# disciples_v1.net
KiCad netlist of a schematic drawn in EAGLE
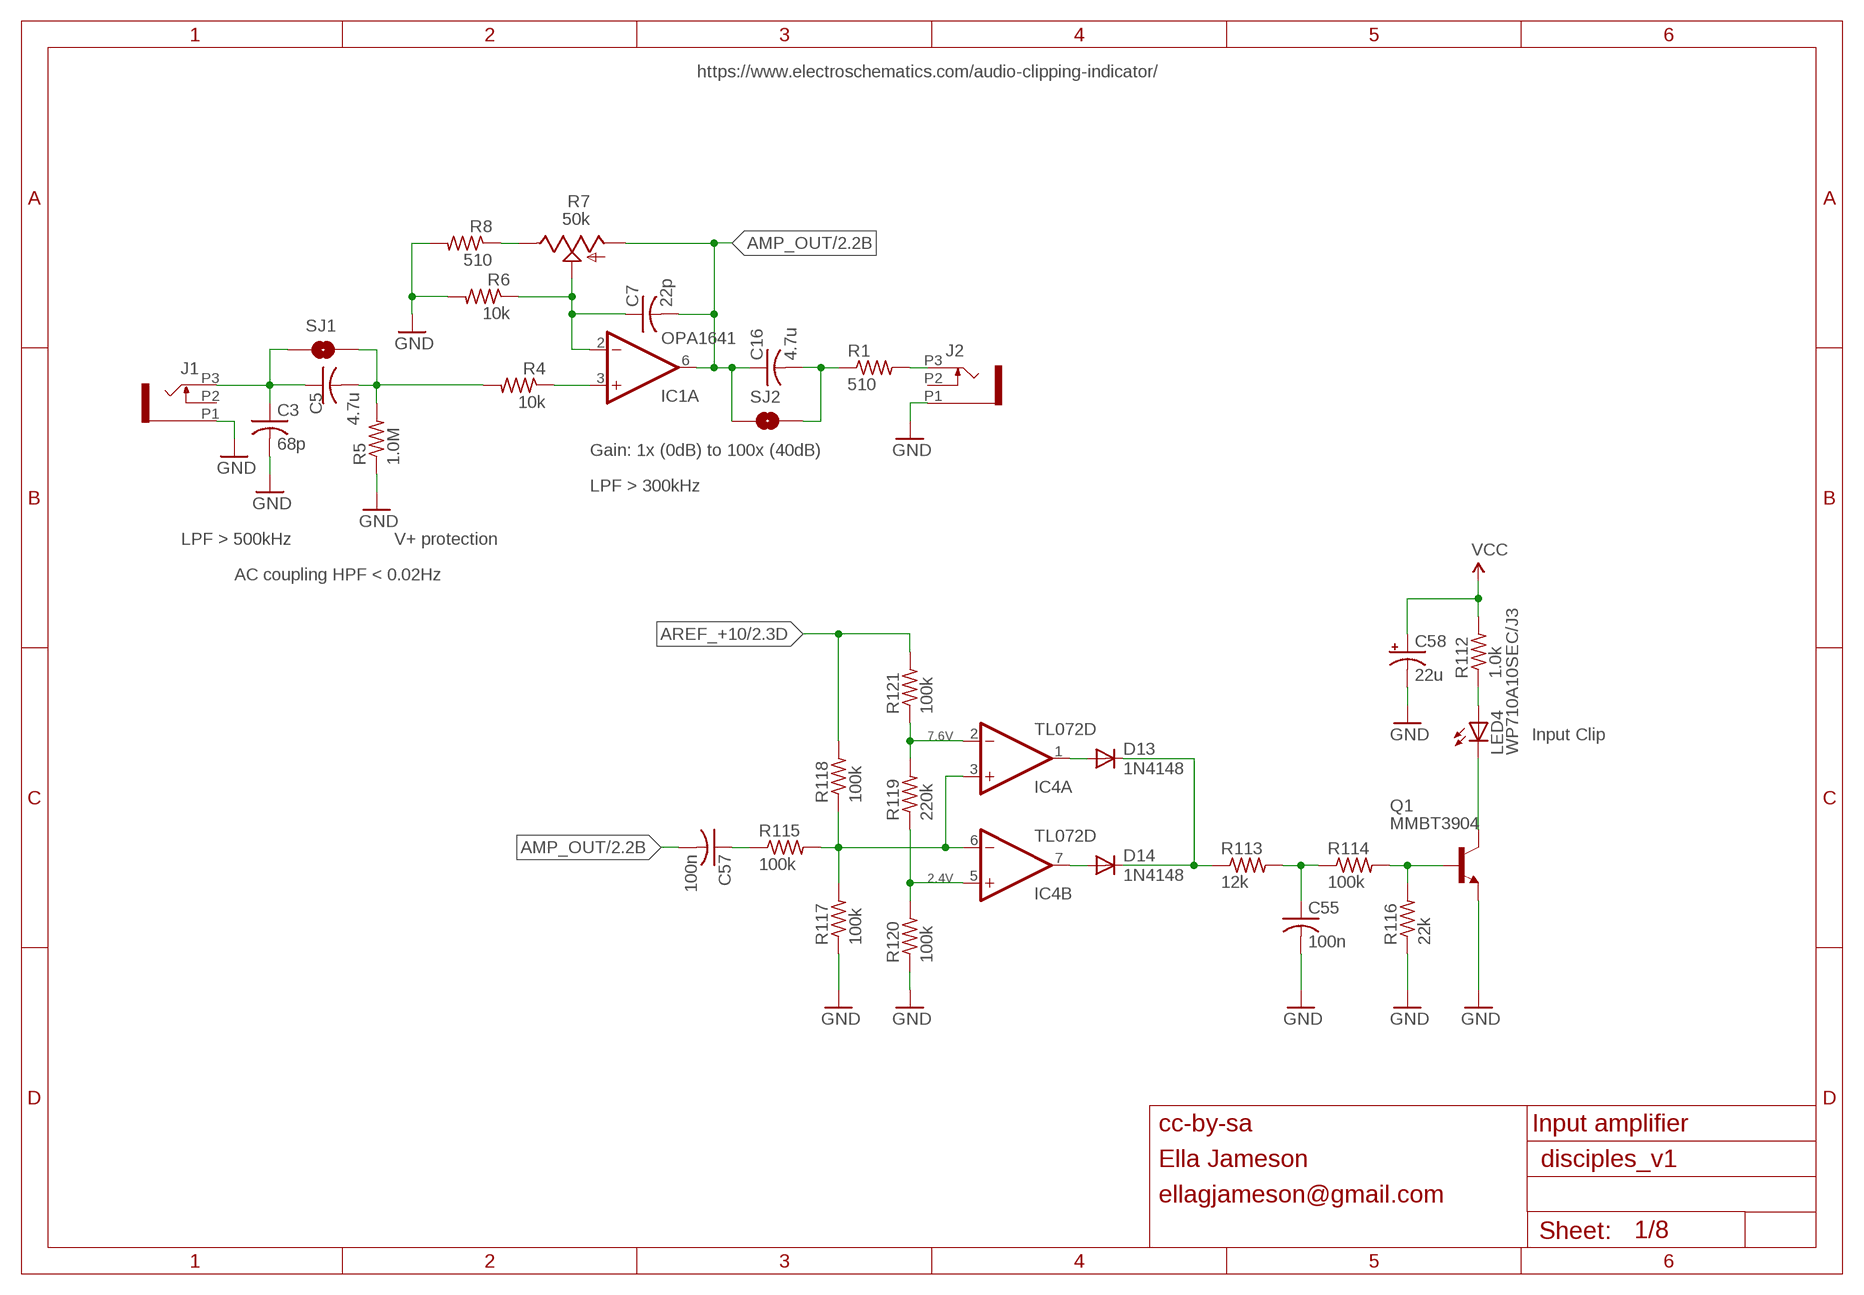
[diagram p0: schematic, sheet 1]
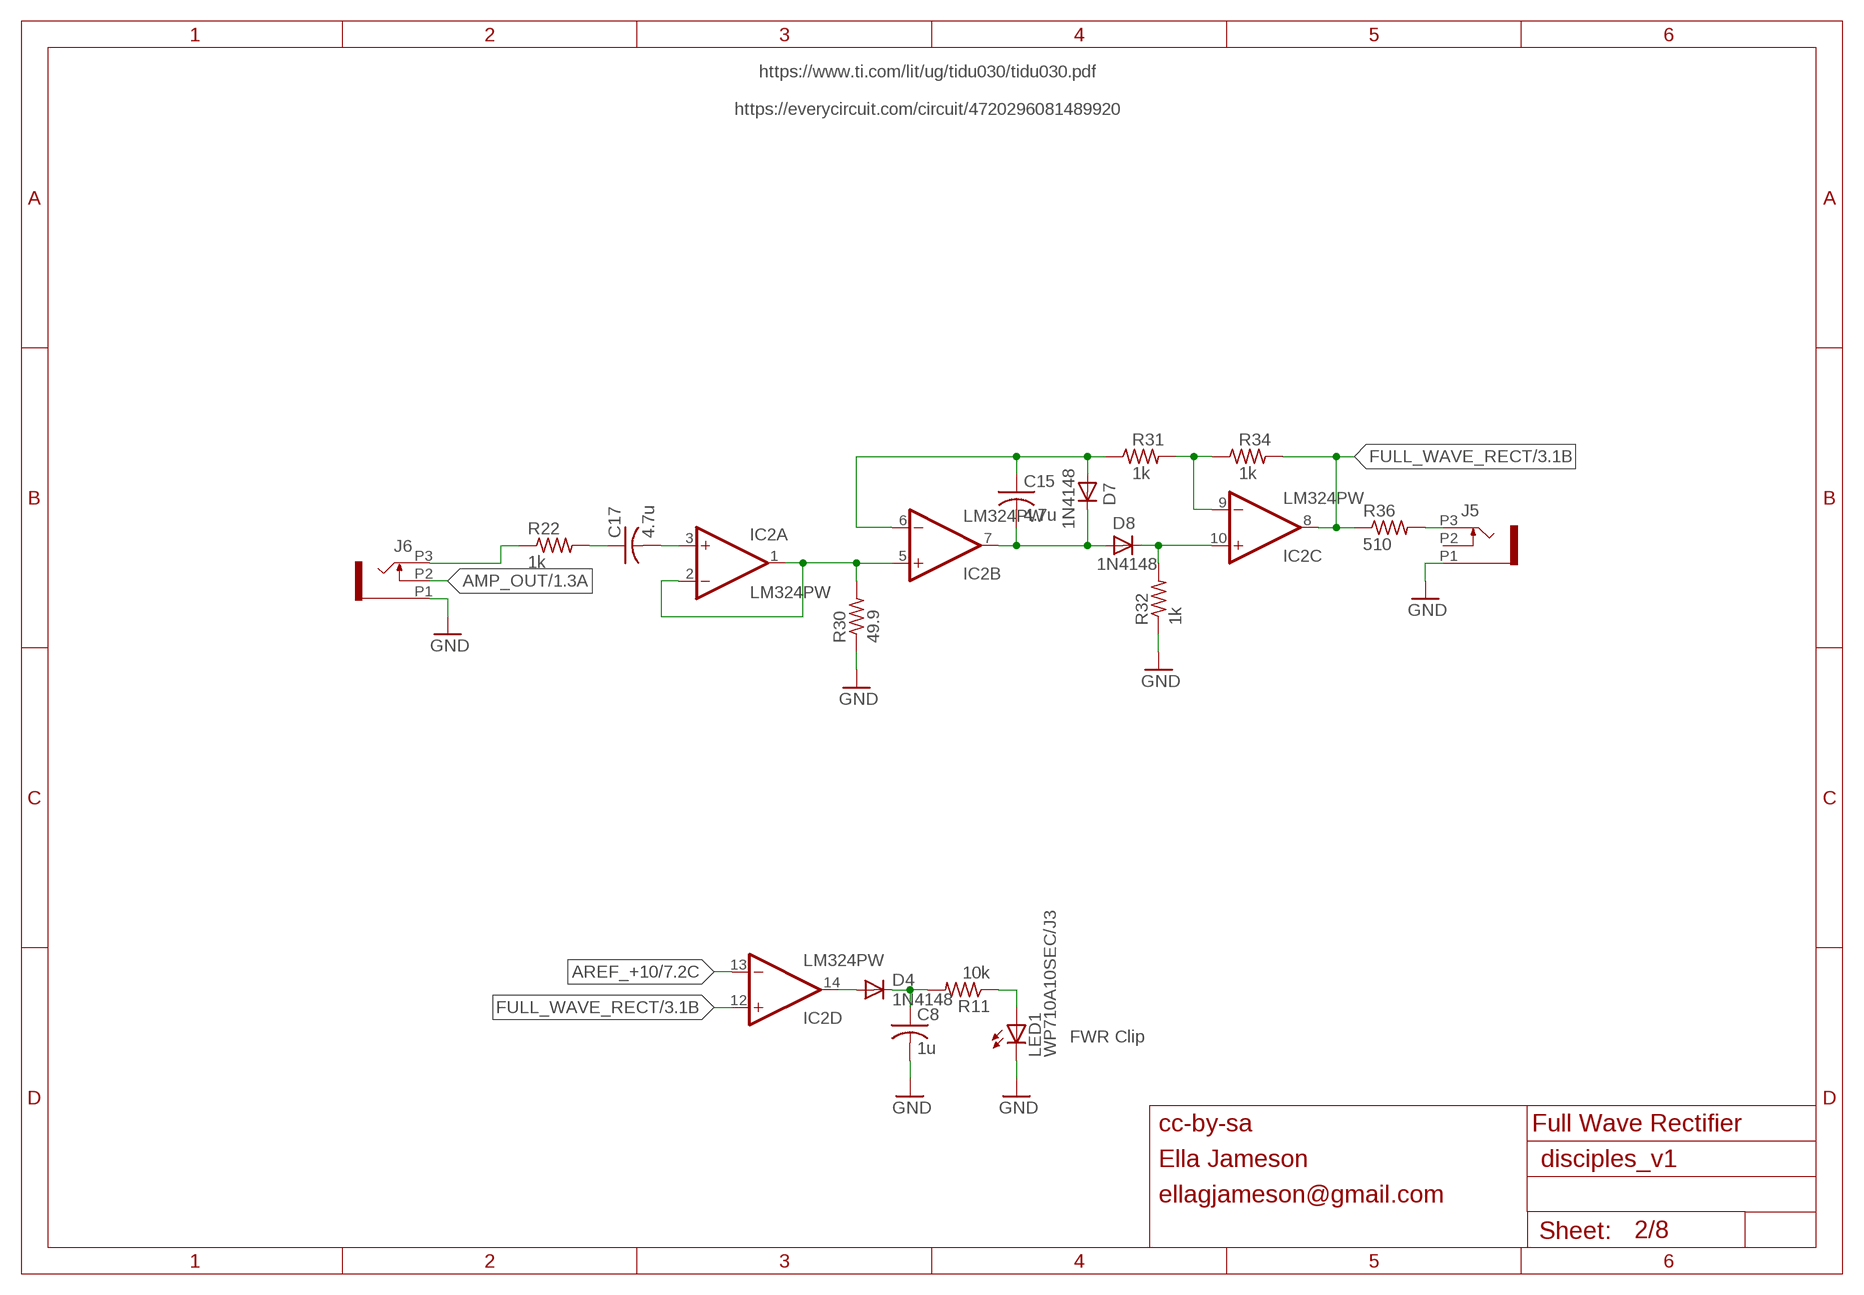
[diagram p1: schematic, sheet 2]
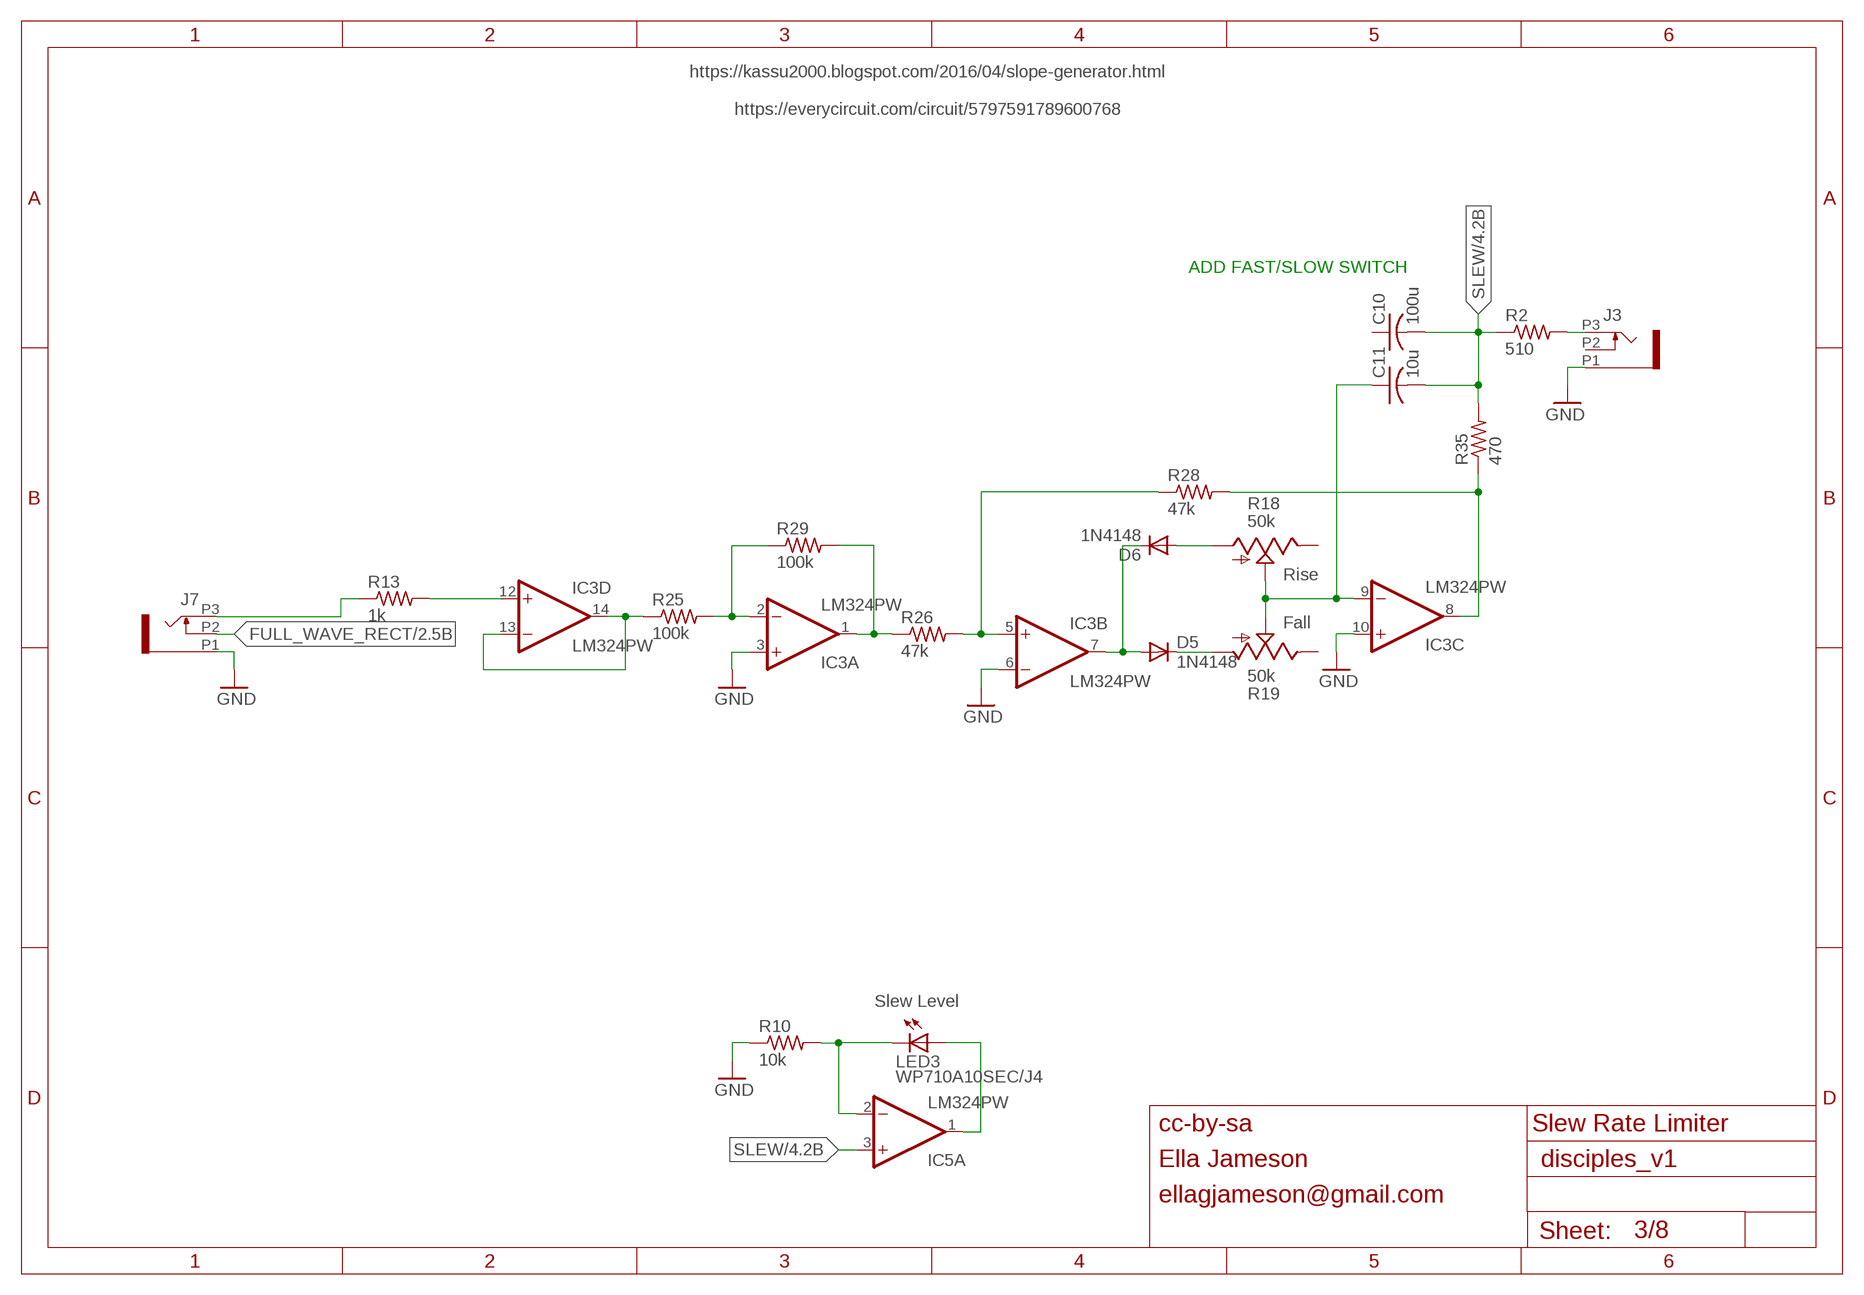
[diagram p2: schematic, sheet 3]
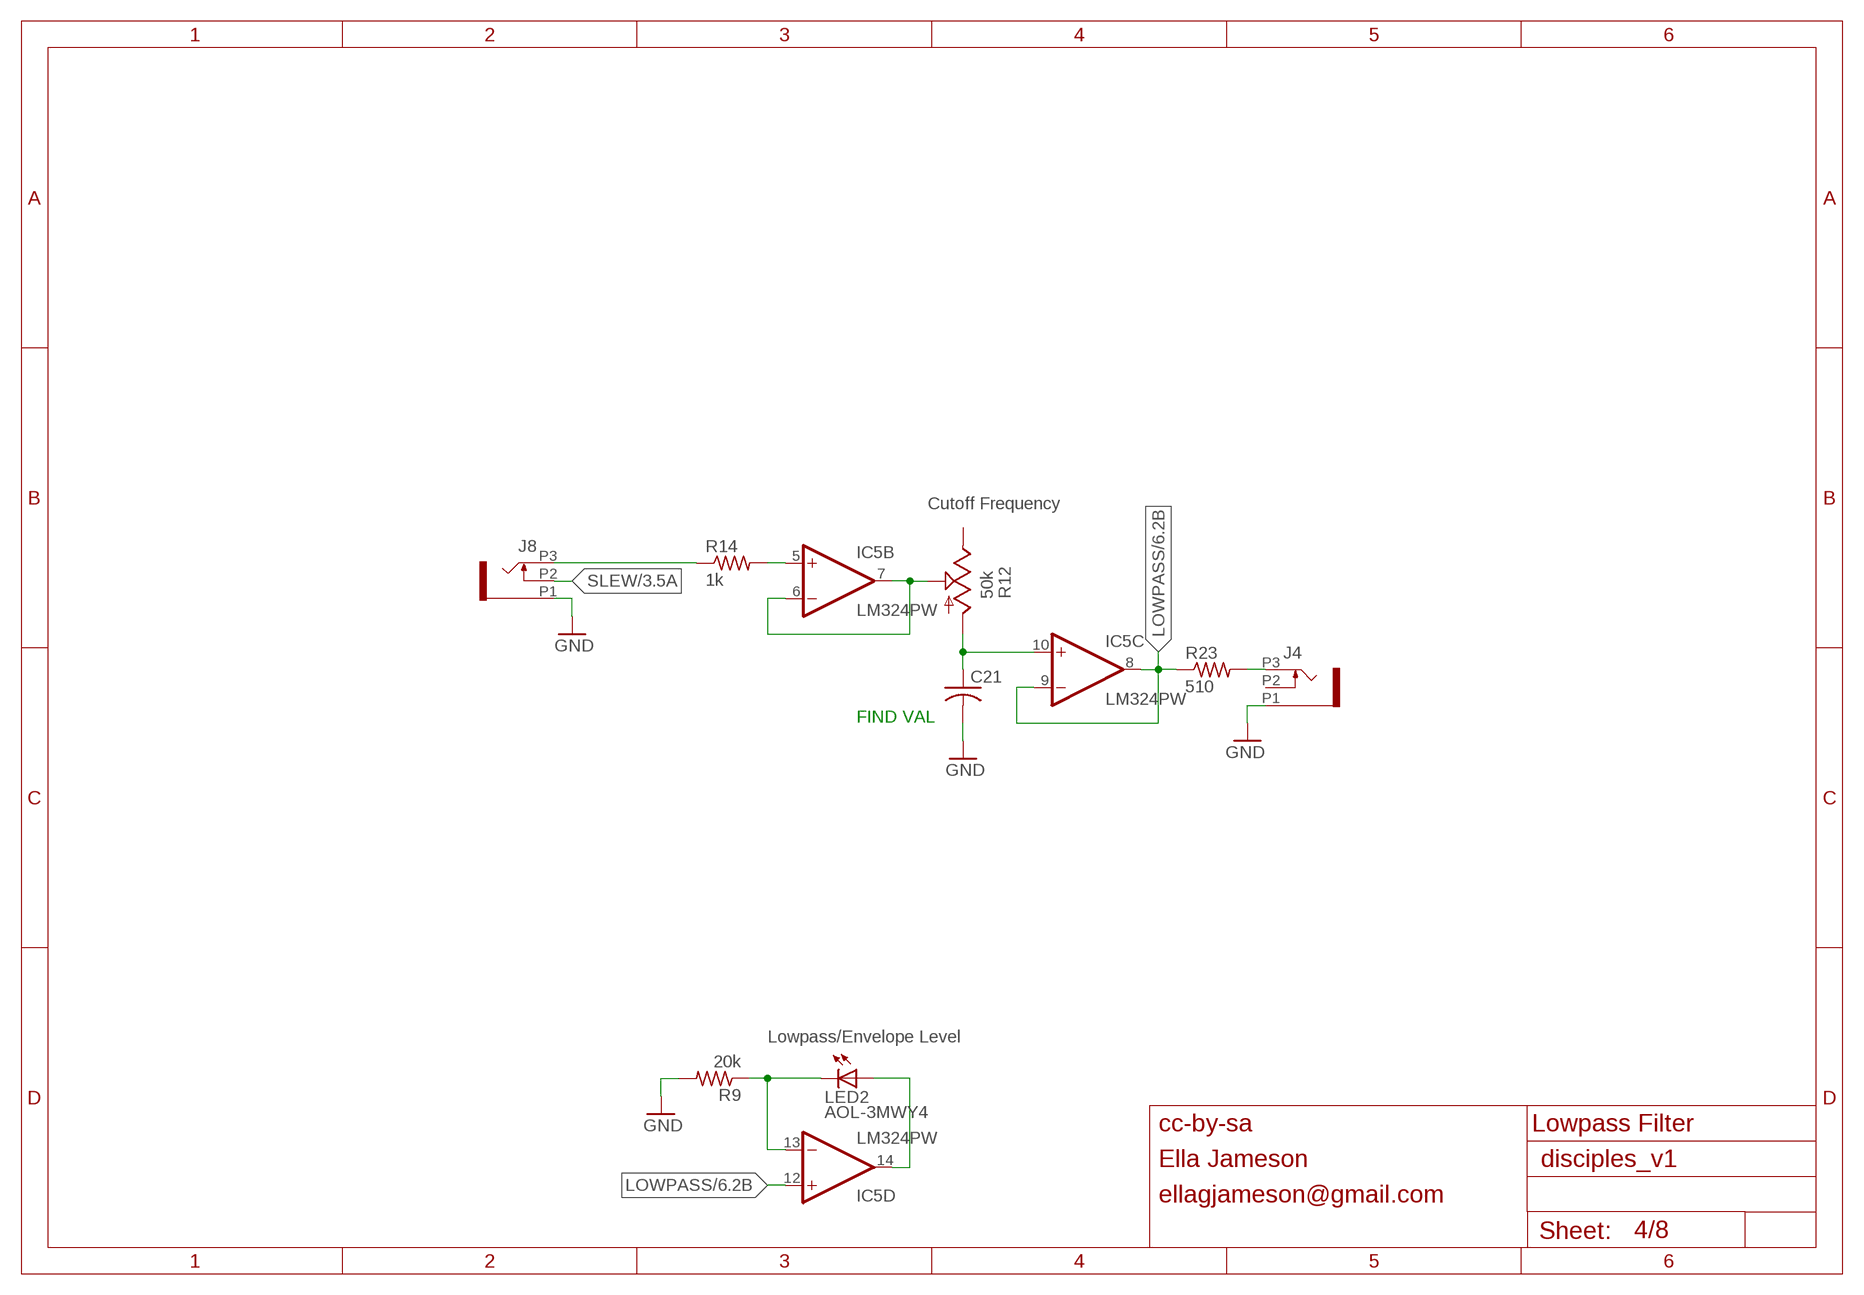
[diagram p3: schematic, sheet 4]
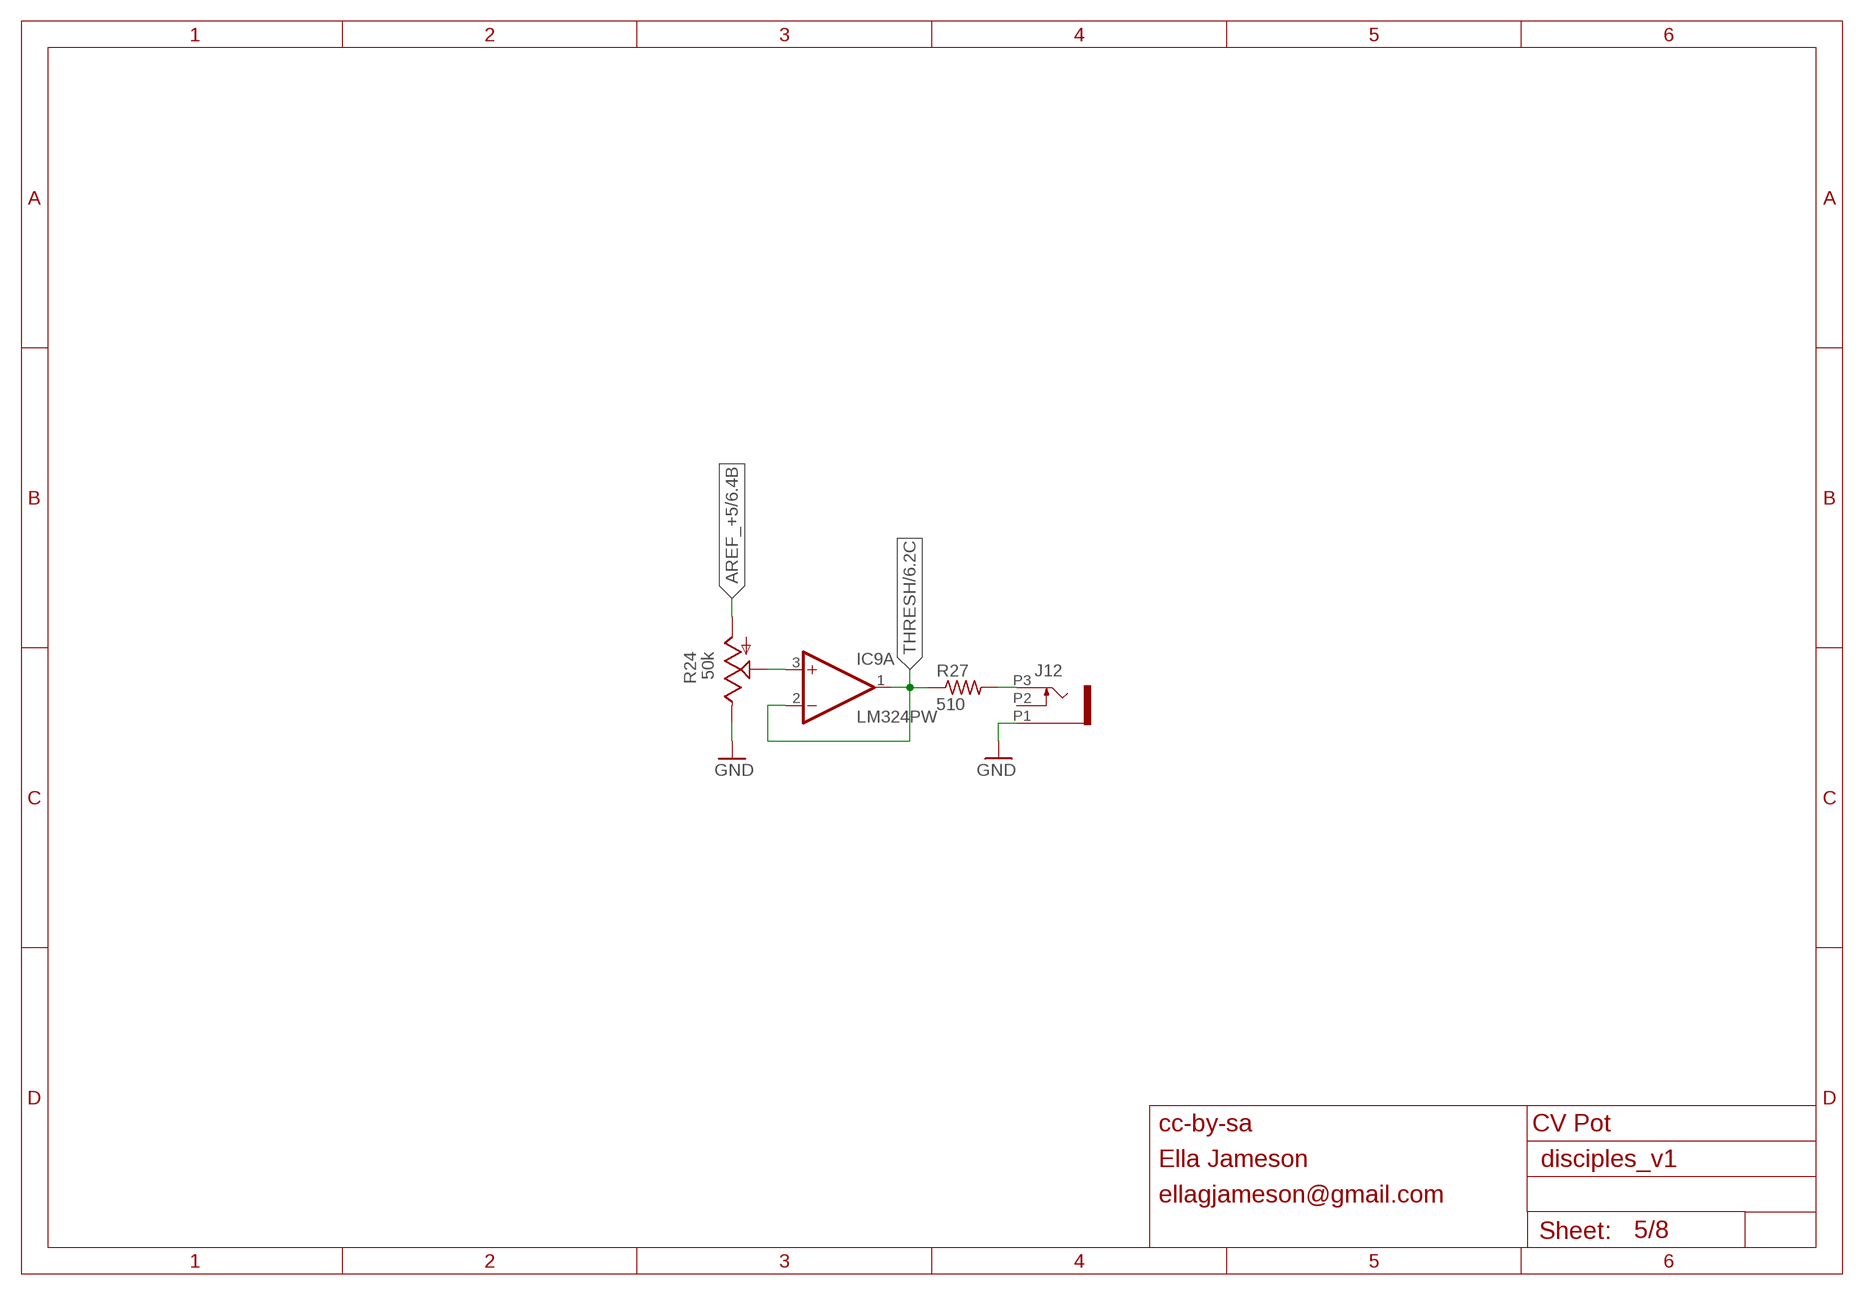
[diagram p4: schematic, sheet 5]
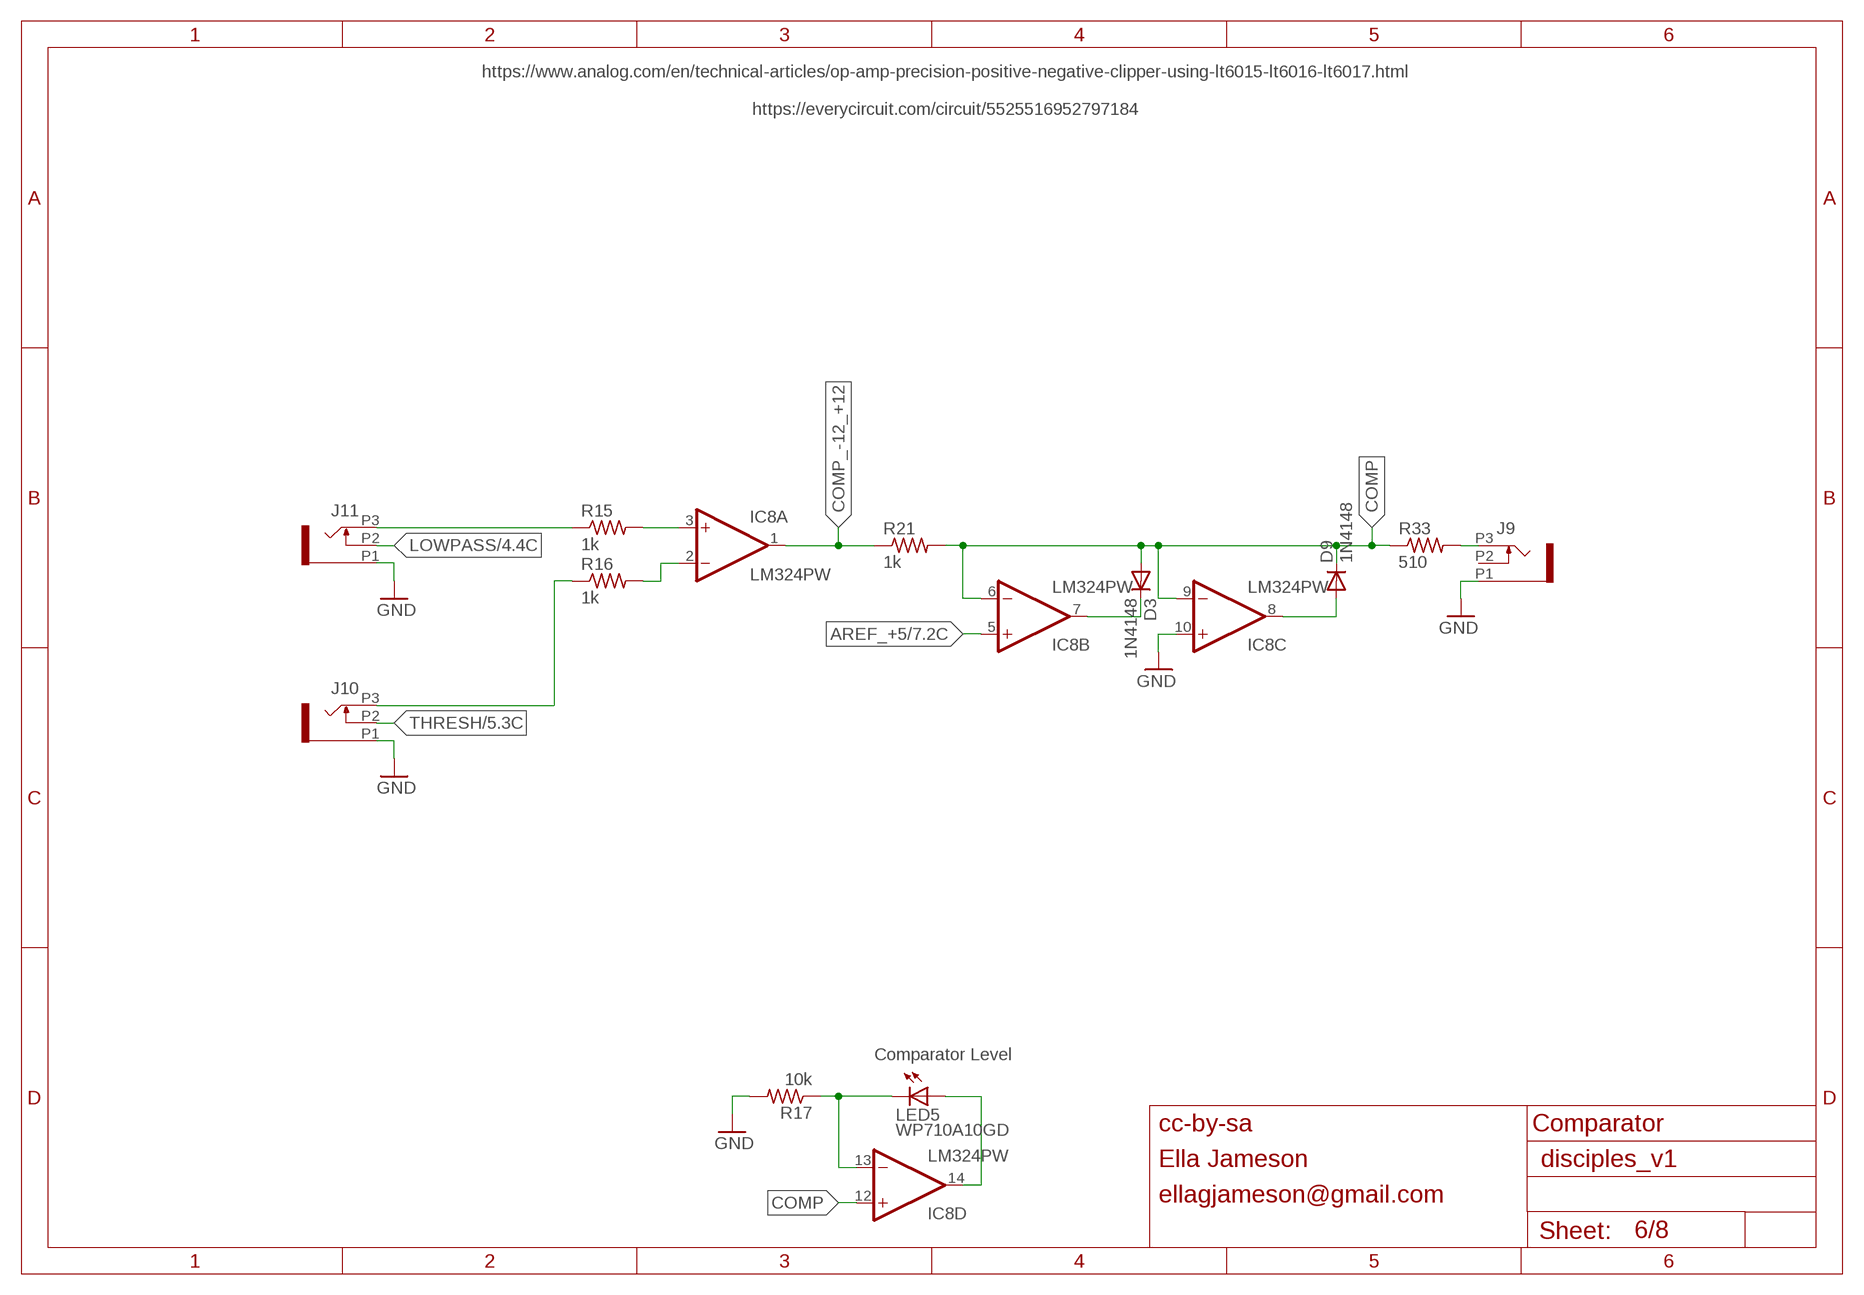
[diagram p5: schematic, sheet 6]
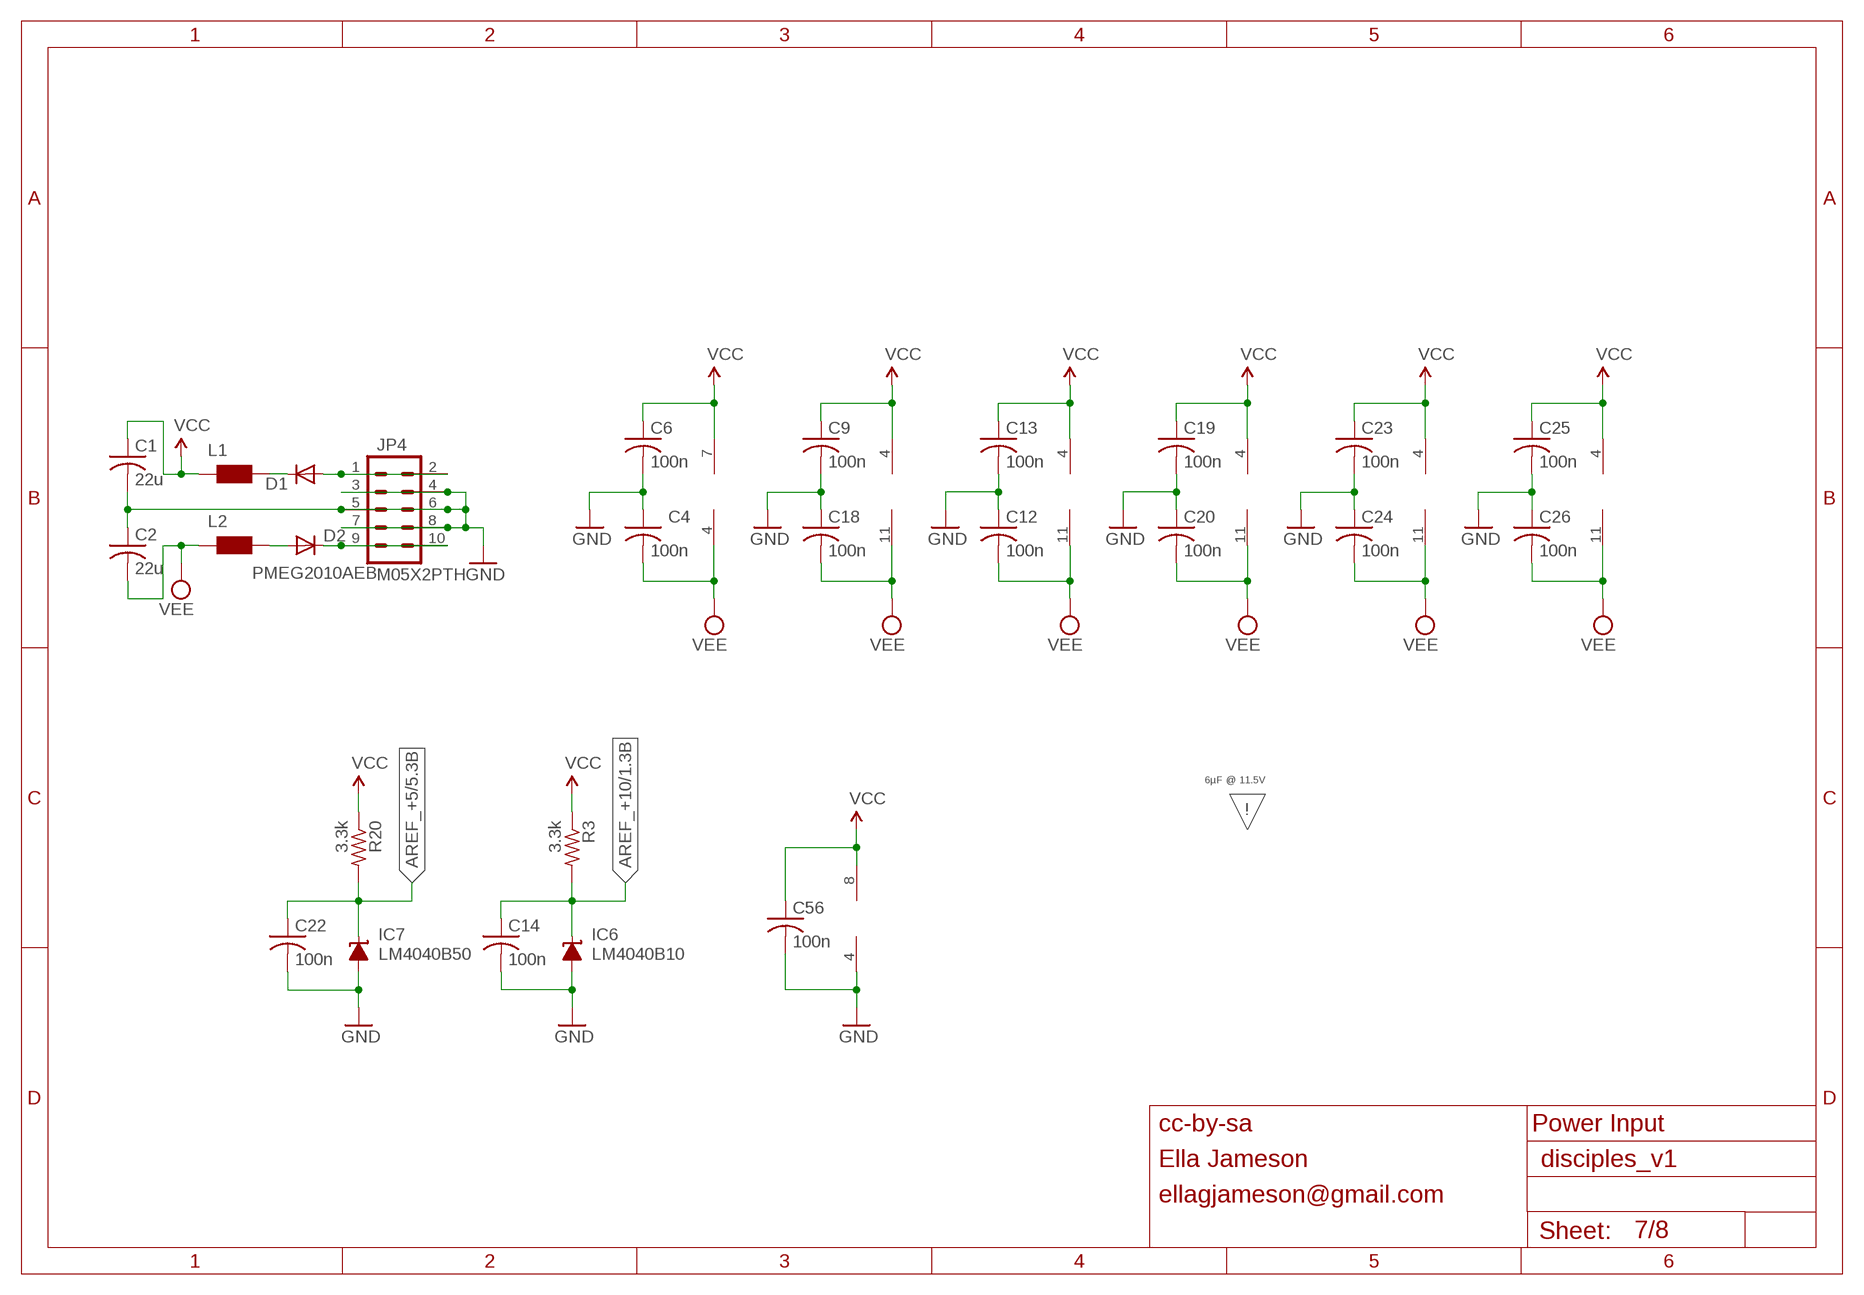
[diagram p6: schematic, sheet 7]
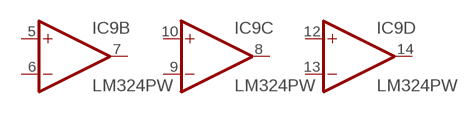
[diagram p7: schematic, sheet 8]

(export (version "E")
  (design (tool "Eeschema 10.0.6"))
  (components
    (comp (ref "C3")
      (value "68p")
      (footprint "eagle-import:C0402")
      (libsource (lib "eagle-import") (part "C-USC0402"))
    )
    (comp (ref "C5")
      (value "4.7u")
      (footprint "eagle-import:C0603")
      (libsource (lib "eagle-import") (part "C-USC0603"))
    )
    (comp (ref "C7")
      (value "22p")
      (footprint "eagle-import:C0402")
      (libsource (lib "eagle-import") (part "C-USC0402"))
    )
    (comp (ref "C16")
      (value "4.7u")
      (footprint "eagle-import:C0603")
      (libsource (lib "eagle-import") (part "C-USC0603"))
    )
    (comp (ref "C55")
      (value "100n")
      (footprint "eagle-import:C0603")
      (libsource (lib "eagle-import") (part "C-USC0603"))
    )
    (comp (ref "C57")
      (value "100n")
      (footprint "eagle-import:C0603")
      (libsource (lib "eagle-import") (part "C-USC0603"))
    )
    (comp (ref "C58")
      (value "22u")
      (footprint "eagle-import:PANASONIC_C")
      (libsource (lib "eagle-import") (part "CPOL-USC"))
    )
    (comp (ref "D13")
      (value "1N4148")
      (footprint "eagle-import:SOD323-W")
      (libsource (lib "eagle-import") (part "DIODE-SOD323-W"))
    )
    (comp (ref "D14")
      (value "1N4148")
      (footprint "eagle-import:SOD323-W")
      (libsource (lib "eagle-import") (part "DIODE-SOD323-W"))
    )
    (comp (ref "IC1")
      (value "OPA1641")
      (footprint "eagle-import:MSOP8")
      (libsource (lib "eagle-import") (part "OPA1641"))
    )
    (comp (ref "IC4")
      (value "TL072D")
      (footprint "eagle-import:SO08")
      (libsource (lib "eagle-import") (part "TL072D"))
    )
    (comp (ref "J1")
      (value "PJ301_THONKICONN6")
      (footprint "eagle-import:WQP_PJ_301M6")
      (libsource (lib "eagle-import") (part "PJ301_THONKICONN6"))
    )
    (comp (ref "J2")
      (value "PJ301_THONKICONN6")
      (footprint "eagle-import:WQP_PJ_301M6")
      (libsource (lib "eagle-import") (part "PJ301_THONKICONN6"))
    )
    (comp (ref "LED4")
      (value "WP710A10SEC/J3")
      (footprint "eagle-import:LED3MM")
      (libsource (lib "eagle-import") (part "LED3MM"))
    )
    (comp (ref "Q1")
      (value "MMBT3904")
      (footprint "eagle-import:SOT23-BEC")
      (libsource (lib "eagle-import") (part "-NPN-SOT23-BECMMBT3904LT1"))
    )
    (comp (ref "R1")
      (value "510")
      (footprint "eagle-import:R0402")
      (libsource (lib "eagle-import") (part "R-US_R0402"))
    )
    (comp (ref "R4")
      (value "10k")
      (footprint "eagle-import:R0402")
      (libsource (lib "eagle-import") (part "R-US_R0402"))
    )
    (comp (ref "R5")
      (value "1.0M")
      (footprint "eagle-import:R0402")
      (libsource (lib "eagle-import") (part "R-US_R0402"))
    )
    (comp (ref "R6")
      (value "10k")
      (footprint "eagle-import:R0402")
      (libsource (lib "eagle-import") (part "R-US_R0402"))
    )
    (comp (ref "R7")
      (value "50k")
      (footprint "eagle-import:ALPS_POT_VERTICAL_PS")
      (libsource (lib "eagle-import") (part "POT_USVERTICAL_PS"))
    )
    (comp (ref "R8")
      (value "510")
      (footprint "eagle-import:R0402")
      (libsource (lib "eagle-import") (part "R-US_R0402"))
    )
    (comp (ref "R112")
      (value "1.0k")
      (footprint "eagle-import:R0603")
      (libsource (lib "eagle-import") (part "R-US_R0603"))
    )
    (comp (ref "R113")
      (value "12k")
      (footprint "eagle-import:R0603")
      (libsource (lib "eagle-import") (part "R-US_R0603"))
    )
    (comp (ref "R114")
      (value "100k")
      (footprint "eagle-import:R0603")
      (libsource (lib "eagle-import") (part "R-US_R0603"))
    )
    (comp (ref "R115")
      (value "100k")
      (footprint "eagle-import:R0603")
      (libsource (lib "eagle-import") (part "R-US_R0603"))
    )
    (comp (ref "R116")
      (value "22k")
      (footprint "eagle-import:R0603")
      (libsource (lib "eagle-import") (part "R-US_R0603"))
    )
    (comp (ref "R117")
      (value "100k")
      (footprint "eagle-import:R0603")
      (libsource (lib "eagle-import") (part "R-US_R0603"))
    )
    (comp (ref "R118")
      (value "100k")
      (footprint "eagle-import:R0603")
      (libsource (lib "eagle-import") (part "R-US_R0603"))
    )
    (comp (ref "R119")
      (value "220k")
      (footprint "eagle-import:R0603")
      (libsource (lib "eagle-import") (part "R-US_R0603"))
    )
    (comp (ref "R120")
      (value "100k")
      (footprint "eagle-import:R0603")
      (libsource (lib "eagle-import") (part "R-US_R0603"))
    )
    (comp (ref "R121")
      (value "100k")
      (footprint "eagle-import:R0603")
      (libsource (lib "eagle-import") (part "R-US_R0603"))
    )
    (comp (ref "SJ1")
      (value "SOLDERJUMPERNC")
      (footprint "eagle-import:SJ_2S")
      (libsource (lib "eagle-import") (part "SOLDERJUMPERNC"))
    )
    (comp (ref "SJ2")
      (value "SOLDERJUMPERNC")
      (footprint "eagle-import:SJ_2S")
      (libsource (lib "eagle-import") (part "SOLDERJUMPERNC"))
    )
    (comp (ref "IC9")
      (value "LM324PW")
      (footprint "eagle-import:TSSOP14")
      (libsource (lib "eagle-import") (part "LM324PW"))
    )
    (comp (ref "J12")
      (value "PJ301_THONKICONN6")
      (footprint "eagle-import:WQP_PJ_301M6")
      (libsource (lib "eagle-import") (part "PJ301_THONKICONN6"))
    )
    (comp (ref "R24")
      (value "50k")
      (footprint "eagle-import:ALPS_POT_VERTICAL_PS")
      (libsource (lib "eagle-import") (part "POT_USVERTICAL_PS"))
    )
    (comp (ref "R27")
      (value "510")
      (footprint "eagle-import:R0402")
      (libsource (lib "eagle-import") (part "R-US_R0402"))
    )
    (comp (ref "C10")
      (value "100u")
      (footprint "eagle-import:C0402")
      (libsource (lib "eagle-import") (part "C-USC0402"))
    )
    (comp (ref "C11")
      (value "10u")
      (footprint "eagle-import:C0402")
      (libsource (lib "eagle-import") (part "C-USC0402"))
    )
    (comp (ref "D5")
      (value "1N4148")
      (footprint "eagle-import:SOD523")
      (libsource (lib "eagle-import") (part "DIODE-SOD523"))
    )
    (comp (ref "D6")
      (value "1N4148")
      (footprint "eagle-import:SOD523")
      (libsource (lib "eagle-import") (part "DIODE-SOD523"))
    )
    (comp (ref "IC3")
      (value "LM324PW")
      (footprint "eagle-import:TSSOP14")
      (libsource (lib "eagle-import") (part "LM324PW"))
    )
    (comp (ref "IC5")
      (value "LM324PW")
      (footprint "eagle-import:TSSOP14")
      (libsource (lib "eagle-import") (part "LM324PW"))
    )
    (comp (ref "J3")
      (value "PJ301_THONKICONN6")
      (footprint "eagle-import:WQP_PJ_301M6")
      (libsource (lib "eagle-import") (part "PJ301_THONKICONN6"))
    )
    (comp (ref "J7")
      (value "PJ301_THONKICONN6")
      (footprint "eagle-import:WQP_PJ_301M6")
      (libsource (lib "eagle-import") (part "PJ301_THONKICONN6"))
    )
    (comp (ref "LED3")
      (value "WP710A10SEC/J4")
      (footprint "eagle-import:LED3MM")
      (libsource (lib "eagle-import") (part "LED3MM"))
    )
    (comp (ref "R2")
      (value "510")
      (footprint "eagle-import:R0402")
      (libsource (lib "eagle-import") (part "R-US_R0402"))
    )
    (comp (ref "R10")
      (value "10k")
      (footprint "eagle-import:R0402")
      (libsource (lib "eagle-import") (part "R-US_R0402"))
    )
    (comp (ref "R13")
      (value "1k")
      (footprint "eagle-import:R0402")
      (libsource (lib "eagle-import") (part "R-US_R0402"))
    )
    (comp (ref "R18")
      (value "50k")
      (footprint "eagle-import:ALPS_POT_VERTICAL_PS")
      (libsource (lib "eagle-import") (part "POT_USVERTICAL_PS"))
    )
    (comp (ref "R19")
      (value "50k")
      (footprint "eagle-import:ALPS_POT_VERTICAL_PS")
      (libsource (lib "eagle-import") (part "POT_USVERTICAL_PS"))
    )
    (comp (ref "R25")
      (value "100k")
      (footprint "eagle-import:R0402")
      (libsource (lib "eagle-import") (part "R-US_R0402"))
    )
    (comp (ref "R26")
      (value "47k")
      (footprint "eagle-import:R0402")
      (libsource (lib "eagle-import") (part "R-US_R0402"))
    )
    (comp (ref "R28")
      (value "47k")
      (footprint "eagle-import:R0402")
      (libsource (lib "eagle-import") (part "R-US_R0402"))
    )
    (comp (ref "R29")
      (value "100k")
      (footprint "eagle-import:R0402")
      (libsource (lib "eagle-import") (part "R-US_R0402"))
    )
    (comp (ref "R35")
      (value "470")
      (footprint "eagle-import:R0402")
      (libsource (lib "eagle-import") (part "R-US_R0402"))
    )
    (comp (ref "C1")
      (value "22u")
      (footprint "eagle-import:C1206")
      (libsource (lib "eagle-import") (part "C-USC1206"))
    )
    (comp (ref "C2")
      (value "22u")
      (footprint "eagle-import:C1206")
      (libsource (lib "eagle-import") (part "C-USC1206"))
    )
    (comp (ref "C4")
      (value "100n")
      (footprint "eagle-import:C0402")
      (libsource (lib "eagle-import") (part "C-USC0402"))
    )
    (comp (ref "C6")
      (value "100n")
      (footprint "eagle-import:C0402")
      (libsource (lib "eagle-import") (part "C-USC0402"))
    )
    (comp (ref "C9")
      (value "100n")
      (footprint "eagle-import:C0402")
      (libsource (lib "eagle-import") (part "C-USC0402"))
    )
    (comp (ref "C12")
      (value "100n")
      (footprint "eagle-import:C0402")
      (libsource (lib "eagle-import") (part "C-USC0402"))
    )
    (comp (ref "C13")
      (value "100n")
      (footprint "eagle-import:C0402")
      (libsource (lib "eagle-import") (part "C-USC0402"))
    )
    (comp (ref "C14")
      (value "100n")
      (footprint "eagle-import:C0603")
      (libsource (lib "eagle-import") (part "C-USC0603"))
    )
    (comp (ref "C18")
      (value "100n")
      (footprint "eagle-import:C0402")
      (libsource (lib "eagle-import") (part "C-USC0402"))
    )
    (comp (ref "C19")
      (value "100n")
      (footprint "eagle-import:C0402")
      (libsource (lib "eagle-import") (part "C-USC0402"))
    )
    (comp (ref "C20")
      (value "100n")
      (footprint "eagle-import:C0402")
      (libsource (lib "eagle-import") (part "C-USC0402"))
    )
    (comp (ref "C22")
      (value "100n")
      (footprint "eagle-import:C0603")
      (libsource (lib "eagle-import") (part "C-USC0603"))
    )
    (comp (ref "C23")
      (value "100n")
      (footprint "eagle-import:C0402")
      (libsource (lib "eagle-import") (part "C-USC0402"))
    )
    (comp (ref "C24")
      (value "100n")
      (footprint "eagle-import:C0402")
      (libsource (lib "eagle-import") (part "C-USC0402"))
    )
    (comp (ref "C25")
      (value "100n")
      (footprint "eagle-import:C0402")
      (libsource (lib "eagle-import") (part "C-USC0402"))
    )
    (comp (ref "C26")
      (value "100n")
      (footprint "eagle-import:C0402")
      (libsource (lib "eagle-import") (part "C-USC0402"))
    )
    (comp (ref "C56")
      (value "100n")
      (footprint "eagle-import:C0603")
      (libsource (lib "eagle-import") (part "C-USC0603"))
    )
    (comp (ref "D1")
      (value "PMEG2010AEB")
      (footprint "eagle-import:SOD523")
      (libsource (lib "eagle-import") (part "DIODE-SOD523"))
    )
    (comp (ref "D2")
      (value "PMEG2010AEB")
      (footprint "eagle-import:SOD523")
      (libsource (lib "eagle-import") (part "DIODE-SOD523"))
    )
    (comp (ref "IC2")
      (value "LM324PW")
      (footprint "eagle-import:TSSOP14")
      (libsource (lib "eagle-import") (part "LM324PW"))
    )
    (comp (ref "IC6")
      (value "LM4040B10")
      (footprint "eagle-import:DBZ_R-PDSO-G3")
      (libsource (lib "eagle-import") (part "LM4041DBZB12"))
    )
    (comp (ref "IC7")
      (value "LM4040B50")
      (footprint "eagle-import:DBZ_R-PDSO-G3")
      (libsource (lib "eagle-import") (part "LM4041DBZB12"))
    )
    (comp (ref "IC8")
      (value "LM324PW")
      (footprint "eagle-import:TSSOP14")
      (libsource (lib "eagle-import") (part "LM324PW"))
    )
    (comp (ref "JP4")
      (value "M05X2PTH")
      (footprint "eagle-import:AVR_ICSP")
      (libsource (lib "eagle-import") (part "M05X2PTH"))
    )
    (comp (ref "L1")
      (value "WE-CBF_0603")
      (footprint "eagle-import:0603")
      (libsource (lib "eagle-import") (part "WE-CBF_0603"))
    )
    (comp (ref "L2")
      (value "WE-CBF_0603")
      (footprint "eagle-import:0603")
      (libsource (lib "eagle-import") (part "WE-CBF_0603"))
    )
    (comp (ref "R3")
      (value "3.3k")
      (footprint "eagle-import:R0603")
      (libsource (lib "eagle-import") (part "R-US_R0603"))
    )
    (comp (ref "R20")
      (value "3.3k")
      (footprint "eagle-import:R0603")
      (libsource (lib "eagle-import") (part "R-US_R0603"))
    )
    (comp (ref "D3")
      (value "1N4148")
      (footprint "eagle-import:SOD523")
      (libsource (lib "eagle-import") (part "DIODE-SOD523"))
    )
    (comp (ref "D9")
      (value "1N4148")
      (footprint "eagle-import:SOD523")
      (libsource (lib "eagle-import") (part "DIODE-SOD523"))
    )
    (comp (ref "J9")
      (value "PJ301_THONKICONN6")
      (footprint "eagle-import:WQP_PJ_301M6")
      (libsource (lib "eagle-import") (part "PJ301_THONKICONN6"))
    )
    (comp (ref "J10")
      (value "PJ301_THONKICONN6")
      (footprint "eagle-import:WQP_PJ_301M6")
      (libsource (lib "eagle-import") (part "PJ301_THONKICONN6"))
    )
    (comp (ref "J11")
      (value "PJ301_THONKICONN6")
      (footprint "eagle-import:WQP_PJ_301M6")
      (libsource (lib "eagle-import") (part "PJ301_THONKICONN6"))
    )
    (comp (ref "LED5")
      (value "WP710A10GD")
      (footprint "eagle-import:LED3MM")
      (libsource (lib "eagle-import") (part "LED3MM"))
    )
    (comp (ref "R15")
      (value "1k")
      (footprint "eagle-import:R0402")
      (libsource (lib "eagle-import") (part "R-US_R0402"))
    )
    (comp (ref "R16")
      (value "1k")
      (footprint "eagle-import:R0402")
      (libsource (lib "eagle-import") (part "R-US_R0402"))
    )
    (comp (ref "R17")
      (value "10k")
      (footprint "eagle-import:R0402")
      (libsource (lib "eagle-import") (part "R-US_R0402"))
    )
    (comp (ref "R21")
      (value "1k")
      (footprint "eagle-import:R0402")
      (libsource (lib "eagle-import") (part "R-US_R0402"))
    )
    (comp (ref "R33")
      (value "510")
      (footprint "eagle-import:R0402")
      (libsource (lib "eagle-import") (part "R-US_R0402"))
    )
    (comp (ref "C8")
      (value "1u")
      (footprint "eagle-import:C0402")
      (libsource (lib "eagle-import") (part "C-USC0402"))
    )
    (comp (ref "C15")
      (value "4.7u")
      (footprint "eagle-import:C0603")
      (libsource (lib "eagle-import") (part "C-USC0603"))
    )
    (comp (ref "C17")
      (value "4.7u")
      (footprint "eagle-import:C0603")
      (libsource (lib "eagle-import") (part "C-USC0603"))
    )
    (comp (ref "D4")
      (value "1N4148")
      (footprint "eagle-import:SOD523")
      (libsource (lib "eagle-import") (part "DIODE-SOD523"))
    )
    (comp (ref "D7")
      (value "1N4148")
      (footprint "eagle-import:SOD523")
      (libsource (lib "eagle-import") (part "DIODE-SOD523"))
    )
    (comp (ref "D8")
      (value "1N4148")
      (footprint "eagle-import:SOD523")
      (libsource (lib "eagle-import") (part "DIODE-SOD523"))
    )
    (comp (ref "J5")
      (value "PJ301_THONKICONN6")
      (footprint "eagle-import:WQP_PJ_301M6")
      (libsource (lib "eagle-import") (part "PJ301_THONKICONN6"))
    )
    (comp (ref "J6")
      (value "PJ301_THONKICONN6")
      (footprint "eagle-import:WQP_PJ_301M6")
      (libsource (lib "eagle-import") (part "PJ301_THONKICONN6"))
    )
    (comp (ref "LED1")
      (value "WP710A10SEC/J3")
      (footprint "eagle-import:LED3MM")
      (libsource (lib "eagle-import") (part "LED3MM"))
    )
    (comp (ref "R11")
      (value "10k")
      (footprint "eagle-import:R0402")
      (libsource (lib "eagle-import") (part "R-US_R0402"))
    )
    (comp (ref "R22")
      (value "1k")
      (footprint "eagle-import:R0402")
      (libsource (lib "eagle-import") (part "R-US_R0402"))
    )
    (comp (ref "R30")
      (value "49.9")
      (footprint "eagle-import:R0402")
      (libsource (lib "eagle-import") (part "R-US_R0402"))
    )
    (comp (ref "R31")
      (value "1k")
      (footprint "eagle-import:R0402")
      (libsource (lib "eagle-import") (part "R-US_R0402"))
    )
    (comp (ref "R32")
      (value "1k")
      (footprint "eagle-import:R0402")
      (libsource (lib "eagle-import") (part "R-US_R0402"))
    )
    (comp (ref "R34")
      (value "1k")
      (footprint "eagle-import:R0402")
      (libsource (lib "eagle-import") (part "R-US_R0402"))
    )
    (comp (ref "R36")
      (value "510")
      (footprint "eagle-import:R0402")
      (libsource (lib "eagle-import") (part "R-US_R0402"))
    )
    (comp (ref "C21")
      (value "C-USC0402")
      (footprint "eagle-import:C0402")
      (libsource (lib "eagle-import") (part "C-USC0402"))
    )
    (comp (ref "J4")
      (value "PJ301_THONKICONN6")
      (footprint "eagle-import:WQP_PJ_301M6")
      (libsource (lib "eagle-import") (part "PJ301_THONKICONN6"))
    )
    (comp (ref "J8")
      (value "PJ301_THONKICONN6")
      (footprint "eagle-import:WQP_PJ_301M6")
      (libsource (lib "eagle-import") (part "PJ301_THONKICONN6"))
    )
    (comp (ref "LED2")
      (value "AOL-3MWY4")
      (footprint "eagle-import:LED3MM")
      (libsource (lib "eagle-import") (part "LED3MM"))
    )
    (comp (ref "R9")
      (value "20k")
      (footprint "eagle-import:R0402")
      (libsource (lib "eagle-import") (part "R-US_R0402"))
    )
    (comp (ref "R12")
      (value "50k")
      (footprint "eagle-import:ALPS_POT_VERTICAL_PS")
      (libsource (lib "eagle-import") (part "POT_USVERTICAL_PS"))
    )
    (comp (ref "R14")
      (value "1k")
      (footprint "eagle-import:R0402")
      (libsource (lib "eagle-import") (part "R-US_R0402"))
    )
    (comp (ref "R23")
      (value "510")
      (footprint "eagle-import:R0402")
      (libsource (lib "eagle-import") (part "R-US_R0402"))
    )
  )
  (nets
    (net (code "1") (name "AMP_OUT") (class "Default")
      (node (ref "C16") (pin "1") (pinfunction "1_1") (pintype "passive"))
      (node (ref "C57") (pin "2") (pinfunction "2_2") (pintype "passive"))
      (node (ref "C7") (pin "2") (pinfunction "2_2") (pintype "passive"))
      (node (ref "IC1") (pin "6") (pinfunction "OUT_6") (pintype "output"))
      (node (ref "J6") (pin "P2") (pinfunction "2_P2") (pintype "passive"))
      (node (ref "R7") (pin "P$3") (pinfunction "A_P$3") (pintype "passive"))
      (node (ref "SJ2") (pin "1") (pinfunction "1_1") (pintype "passive"))
    )
    (net (code "2") (name "AREF_+5") (class "Default")
      (node (ref "C22") (pin "1") (pinfunction "1_1") (pintype "passive"))
      (node (ref "IC7") (pin "1") (pinfunction "C_1") (pintype "passive"))
      (node (ref "IC8") (pin "5") (pinfunction "+IN_5") (pintype "input"))
      (node (ref "R20") (pin "2") (pinfunction "2_2") (pintype "passive"))
      (node (ref "R24") (pin "P$3") (pinfunction "A_P$3") (pintype "passive"))
    )
    (net (code "3") (name "AREF_+10") (class "Default")
      (node (ref "C14") (pin "1") (pinfunction "1_1") (pintype "passive"))
      (node (ref "IC2") (pin "13") (pinfunction "-IN_13") (pintype "input"))
      (node (ref "IC6") (pin "1") (pinfunction "C_1") (pintype "passive"))
      (node (ref "R118") (pin "2") (pinfunction "2_2") (pintype "passive"))
      (node (ref "R121") (pin "2") (pinfunction "2_2") (pintype "passive"))
      (node (ref "R3") (pin "2") (pinfunction "2_2") (pintype "passive"))
    )
    (net (code "4") (name "COMP") (class "Default")
      (node (ref "D3") (pin "A") (pinfunction "A_A") (pintype "passive"))
      (node (ref "D9") (pin "C") (pinfunction "C_C") (pintype "passive"))
      (node (ref "IC8") (pin "12") (pinfunction "+IN_12") (pintype "input"))
      (node (ref "IC8") (pin "6") (pinfunction "-IN_6") (pintype "input"))
      (node (ref "IC8") (pin "9") (pinfunction "-IN_9") (pintype "input"))
      (node (ref "R21") (pin "2") (pinfunction "2_2") (pintype "passive"))
      (node (ref "R33") (pin "1") (pinfunction "1_1") (pintype "passive"))
    )
    (net (code "5") (name "COMP_-12_+12") (class "Default")
      (node (ref "IC8") (pin "1") (pinfunction "OUT_1") (pintype "output"))
      (node (ref "R21") (pin "1") (pinfunction "1_1") (pintype "passive"))
    )
    (net (code "6") (name "FULL_WAVE_RECT") (class "Default")
      (node (ref "IC2") (pin "12") (pinfunction "+IN_12") (pintype "input"))
      (node (ref "IC2") (pin "8") (pinfunction "OUT_8") (pintype "output"))
      (node (ref "J7") (pin "P2") (pinfunction "2_P2") (pintype "passive"))
      (node (ref "R34") (pin "2") (pinfunction "2_2") (pintype "passive"))
      (node (ref "R36") (pin "1") (pinfunction "1_1") (pintype "passive"))
    )
    (net (code "7") (name "GND") (class "Default")
      (node (ref "C1") (pin "2") (pinfunction "2_2") (pintype "passive"))
      (node (ref "C12") (pin "1") (pinfunction "1_1") (pintype "passive"))
      (node (ref "C13") (pin "2") (pinfunction "2_2") (pintype "passive"))
      (node (ref "C14") (pin "2") (pinfunction "2_2") (pintype "passive"))
      (node (ref "C18") (pin "1") (pinfunction "1_1") (pintype "passive"))
      (node (ref "C19") (pin "2") (pinfunction "2_2") (pintype "passive"))
      (node (ref "C2") (pin "1") (pinfunction "1_1") (pintype "passive"))
      (node (ref "C20") (pin "1") (pinfunction "1_1") (pintype "passive"))
      (node (ref "C21") (pin "2") (pinfunction "2_2") (pintype "passive"))
      (node (ref "C22") (pin "2") (pinfunction "2_2") (pintype "passive"))
      (node (ref "C23") (pin "2") (pinfunction "2_2") (pintype "passive"))
      (node (ref "C24") (pin "1") (pinfunction "1_1") (pintype "passive"))
      (node (ref "C25") (pin "2") (pinfunction "2_2") (pintype "passive"))
      (node (ref "C26") (pin "1") (pinfunction "1_1") (pintype "passive"))
      (node (ref "C3") (pin "2") (pinfunction "2_2") (pintype "passive"))
      (node (ref "C4") (pin "1") (pinfunction "1_1") (pintype "passive"))
      (node (ref "C55") (pin "2") (pinfunction "2_2") (pintype "passive"))
      (node (ref "C56") (pin "2") (pinfunction "2_2") (pintype "passive"))
      (node (ref "C58") (pin "-") (pinfunction "-_-") (pintype "passive"))
      (node (ref "C6") (pin "2") (pinfunction "2_2") (pintype "passive"))
      (node (ref "C8") (pin "2") (pinfunction "2_2") (pintype "passive"))
      (node (ref "C9") (pin "2") (pinfunction "2_2") (pintype "passive"))
      (node (ref "IC3") (pin "10") (pinfunction "+IN_10") (pintype "input"))
      (node (ref "IC3") (pin "3") (pinfunction "+IN_3") (pintype "input"))
      (node (ref "IC3") (pin "6") (pinfunction "-IN_6") (pintype "input"))
      (node (ref "IC4") (pin "4") (pinfunction "V-_4") (pintype "power_in"))
      (node (ref "IC6") (pin "2") (pinfunction "A_2") (pintype "passive"))
      (node (ref "IC7") (pin "2") (pinfunction "A_2") (pintype "passive"))
      (node (ref "IC8") (pin "10") (pinfunction "+IN_10") (pintype "input"))
      (node (ref "J1") (pin "P1") (pinfunction "1_P1") (pintype "passive"))
      (node (ref "J10") (pin "P1") (pinfunction "1_P1") (pintype "passive"))
      (node (ref "J11") (pin "P1") (pinfunction "1_P1") (pintype "passive"))
      (node (ref "J12") (pin "P1") (pinfunction "1_P1") (pintype "passive"))
      (node (ref "J2") (pin "P1") (pinfunction "1_P1") (pintype "passive"))
      (node (ref "J3") (pin "P1") (pinfunction "1_P1") (pintype "passive"))
      (node (ref "J4") (pin "P1") (pinfunction "1_P1") (pintype "passive"))
      (node (ref "J5") (pin "P1") (pinfunction "1_P1") (pintype "passive"))
      (node (ref "J6") (pin "P1") (pinfunction "1_P1") (pintype "passive"))
      (node (ref "J7") (pin "P1") (pinfunction "1_P1") (pintype "passive"))
      (node (ref "J8") (pin "P1") (pinfunction "1_P1") (pintype "passive"))
      (node (ref "J9") (pin "P1") (pinfunction "1_P1") (pintype "passive"))
      (node (ref "JP4") (pin "3") (pinfunction "3_3") (pintype "passive"))
      (node (ref "JP4") (pin "4") (pinfunction "4_4") (pintype "passive"))
      (node (ref "JP4") (pin "5") (pinfunction "5_5") (pintype "passive"))
      (node (ref "JP4") (pin "6") (pinfunction "6_6") (pintype "passive"))
      (node (ref "JP4") (pin "7") (pinfunction "7_7") (pintype "passive"))
      (node (ref "JP4") (pin "8") (pinfunction "8_8") (pintype "passive"))
      (node (ref "LED1") (pin "K") (pinfunction "C_K") (pintype "passive"))
      (node (ref "Q1") (pin "E") (pinfunction "E_E") (pintype "passive"))
      (node (ref "R10") (pin "1") (pinfunction "1_1") (pintype "passive"))
      (node (ref "R116") (pin "1") (pinfunction "1_1") (pintype "passive"))
      (node (ref "R117") (pin "1") (pinfunction "1_1") (pintype "passive"))
      (node (ref "R120") (pin "1") (pinfunction "1_1") (pintype "passive"))
      (node (ref "R17") (pin "2") (pinfunction "2_2") (pintype "passive"))
      (node (ref "R24") (pin "P$1") (pinfunction "E_P$1") (pintype "passive"))
      (node (ref "R30") (pin "1") (pinfunction "1_1") (pintype "passive"))
      (node (ref "R32") (pin "1") (pinfunction "1_1") (pintype "passive"))
      (node (ref "R5") (pin "1") (pinfunction "1_1") (pintype "passive"))
      (node (ref "R6") (pin "2") (pinfunction "2_2") (pintype "passive"))
      (node (ref "R8") (pin "2") (pinfunction "2_2") (pintype "passive"))
      (node (ref "R9") (pin "2") (pinfunction "2_2") (pintype "passive"))
    )
    (net (code "8") (name "LOWPASS") (class "Default")
      (node (ref "IC5") (pin "12") (pinfunction "+IN_12") (pintype "input"))
      (node (ref "IC5") (pin "8") (pinfunction "OUT_8") (pintype "output"))
      (node (ref "IC5") (pin "9") (pinfunction "-IN_9") (pintype "input"))
      (node (ref "J11") (pin "P2") (pinfunction "2_P2") (pintype "passive"))
      (node (ref "R23") (pin "1") (pinfunction "1_1") (pintype "passive"))
    )
    (net (code "9") (name "Net-(C5-Pad2)") (class "Default")
      (node (ref "C5") (pin "2") (pinfunction "2_2") (pintype "passive"))
      (node (ref "R4") (pin "2") (pinfunction "2_2") (pintype "passive"))
      (node (ref "R5") (pin "2") (pinfunction "2_2") (pintype "passive"))
      (node (ref "SJ1") (pin "2") (pinfunction "2_2") (pintype "passive"))
    )
    (net (code "10") (name "Net-(C8-Pad1)") (class "Default")
      (node (ref "C8") (pin "1") (pinfunction "1_1") (pintype "passive"))
      (node (ref "D4") (pin "C") (pinfunction "C_C") (pintype "passive"))
      (node (ref "R11") (pin "2") (pinfunction "2_2") (pintype "passive"))
    )
    (net (code "11") (name "Net-(C16-Pad2)") (class "Default")
      (node (ref "C16") (pin "2") (pinfunction "2_2") (pintype "passive"))
      (node (ref "R1") (pin "1") (pinfunction "1_1") (pintype "passive"))
      (node (ref "SJ2") (pin "2") (pinfunction "2_2") (pintype "passive"))
    )
    (net (code "12") (name "Net-(C17-Pad1)") (class "Default")
      (node (ref "C17") (pin "1") (pinfunction "1_1") (pintype "passive"))
      (node (ref "R22") (pin "2") (pinfunction "2_2") (pintype "passive"))
    )
    (net (code "13") (name "Net-(C55-Pad1)") (class "Default")
      (node (ref "C55") (pin "1") (pinfunction "1_1") (pintype "passive"))
      (node (ref "R113") (pin "2") (pinfunction "2_2") (pintype "passive"))
      (node (ref "R114") (pin "1") (pinfunction "1_1") (pintype "passive"))
    )
    (net (code "14") (name "Net-(C57-Pad1)") (class "Default")
      (node (ref "C57") (pin "1") (pinfunction "1_1") (pintype "passive"))
      (node (ref "R115") (pin "1") (pinfunction "1_1") (pintype "passive"))
    )
    (net (code "15") (name "Net-(D1-PadA)") (class "Default")
      (node (ref "D1") (pin "A") (pinfunction "A_A") (pintype "passive"))
      (node (ref "JP4") (pin "1") (pinfunction "1_1") (pintype "passive"))
      (node (ref "JP4") (pin "2") (pinfunction "2_2") (pintype "passive"))
    )
    (net (code "16") (name "Net-(D1-PadC)") (class "Default")
      (node (ref "D1") (pin "C") (pinfunction "C_C") (pintype "passive"))
      (node (ref "L1") (pin "2") (pinfunction "2_2") (pintype "passive"))
    )
    (net (code "17") (name "Net-(D2-PadA)") (class "Default")
      (node (ref "D2") (pin "A") (pinfunction "A_A") (pintype "passive"))
      (node (ref "L2") (pin "2") (pinfunction "2_2") (pintype "passive"))
    )
    (net (code "18") (name "Net-(D2-PadC)") (class "Default")
      (node (ref "D2") (pin "C") (pinfunction "C_C") (pintype "passive"))
      (node (ref "JP4") (pin "10") (pinfunction "10_10") (pintype "passive"))
      (node (ref "JP4") (pin "9") (pinfunction "9_9") (pintype "passive"))
    )
    (net (code "19") (name "Net-(D13-PadC)") (class "Default")
      (node (ref "D13") (pin "C") (pinfunction "C_C") (pintype "passive"))
      (node (ref "D14") (pin "C") (pinfunction "C_C") (pintype "passive"))
      (node (ref "R113") (pin "1") (pinfunction "1_1") (pintype "passive"))
    )
    (net (code "20") (name "Net-(IC1A-+IN)") (class "Default")
      (node (ref "IC1") (pin "3") (pinfunction "+IN_3") (pintype "input"))
      (node (ref "R4") (pin "1") (pinfunction "1_1") (pintype "passive"))
    )
    (net (code "21") (name "Net-(IC1A--IN)") (class "Default")
      (node (ref "C7") (pin "1") (pinfunction "1_1") (pintype "passive"))
      (node (ref "IC1") (pin "2") (pinfunction "-IN_2") (pintype "input"))
      (node (ref "R6") (pin "1") (pinfunction "1_1") (pintype "passive"))
      (node (ref "R7") (pin "P$2") (pinfunction "S_P$2") (pintype "passive"))
    )
    (net (code "22") (name "Net-(IC2A-+IN)") (class "Default")
      (node (ref "C17") (pin "2") (pinfunction "2_2") (pintype "passive"))
      (node (ref "IC2") (pin "3") (pinfunction "+IN_3") (pintype "input"))
    )
    (net (code "23") (name "Net-(IC2A--IN)") (class "Default")
      (node (ref "IC2") (pin "1") (pinfunction "OUT_1") (pintype "output"))
      (node (ref "IC2") (pin "2") (pinfunction "-IN_2") (pintype "input"))
      (node (ref "IC2") (pin "5") (pinfunction "+IN_5") (pintype "input"))
      (node (ref "R30") (pin "2") (pinfunction "2_2") (pintype "passive"))
    )
    (net (code "24") (name "Net-(IC2B--IN)") (class "Default")
      (node (ref "C15") (pin "1") (pinfunction "1_1") (pintype "passive"))
      (node (ref "D7") (pin "A") (pinfunction "A_A") (pintype "passive"))
      (node (ref "IC2") (pin "6") (pinfunction "-IN_6") (pintype "input"))
      (node (ref "R31") (pin "1") (pinfunction "1_1") (pintype "passive"))
    )
    (net (code "25") (name "Net-(IC2B-OUT)") (class "Default")
      (node (ref "C15") (pin "2") (pinfunction "2_2") (pintype "passive"))
      (node (ref "D7") (pin "C") (pinfunction "C_C") (pintype "passive"))
      (node (ref "D8") (pin "A") (pinfunction "A_A") (pintype "passive"))
      (node (ref "IC2") (pin "7") (pinfunction "OUT_7") (pintype "output"))
    )
    (net (code "26") (name "Net-(IC2C-+IN)") (class "Default")
      (node (ref "D8") (pin "C") (pinfunction "C_C") (pintype "passive"))
      (node (ref "IC2") (pin "10") (pinfunction "+IN_10") (pintype "input"))
      (node (ref "R32") (pin "2") (pinfunction "2_2") (pintype "passive"))
    )
    (net (code "27") (name "Net-(IC2C--IN)") (class "Default")
      (node (ref "IC2") (pin "9") (pinfunction "-IN_9") (pintype "input"))
      (node (ref "R31") (pin "2") (pinfunction "2_2") (pintype "passive"))
      (node (ref "R34") (pin "1") (pinfunction "1_1") (pintype "passive"))
    )
    (net (code "28") (name "Net-(IC2D-OUT)") (class "Default")
      (node (ref "D4") (pin "A") (pinfunction "A_A") (pintype "passive"))
      (node (ref "IC2") (pin "14") (pinfunction "OUT_14") (pintype "output"))
    )
    (net (code "29") (name "Net-(IC3A--IN)") (class "Default")
      (node (ref "IC3") (pin "2") (pinfunction "-IN_2") (pintype "input"))
      (node (ref "R25") (pin "2") (pinfunction "2_2") (pintype "passive"))
      (node (ref "R29") (pin "1") (pinfunction "1_1") (pintype "passive"))
    )
    (net (code "30") (name "Net-(IC3A-OUT)") (class "Default")
      (node (ref "IC3") (pin "1") (pinfunction "OUT_1") (pintype "output"))
      (node (ref "R26") (pin "1") (pinfunction "1_1") (pintype "passive"))
      (node (ref "R29") (pin "2") (pinfunction "2_2") (pintype "passive"))
    )
    (net (code "31") (name "Net-(IC3B-+IN)") (class "Default")
      (node (ref "IC3") (pin "5") (pinfunction "+IN_5") (pintype "input"))
      (node (ref "R26") (pin "2") (pinfunction "2_2") (pintype "passive"))
      (node (ref "R28") (pin "1") (pinfunction "1_1") (pintype "passive"))
    )
    (net (code "32") (name "Net-(IC3B-OUT)") (class "Default")
      (node (ref "D5") (pin "A") (pinfunction "A_A") (pintype "passive"))
      (node (ref "D6") (pin "C") (pinfunction "C_C") (pintype "passive"))
      (node (ref "IC3") (pin "7") (pinfunction "OUT_7") (pintype "output"))
    )
    (net (code "33") (name "Net-(IC3C--IN)") (class "Default")
      (node (ref "C11") (pin "1") (pinfunction "1_1") (pintype "passive"))
      (node (ref "IC3") (pin "9") (pinfunction "-IN_9") (pintype "input"))
      (node (ref "R18") (pin "P$2") (pinfunction "S_P$2") (pintype "passive"))
      (node (ref "R19") (pin "P$2") (pinfunction "S_P$2") (pintype "passive"))
    )
    (net (code "34") (name "Net-(IC3C-OUT)") (class "Default")
      (node (ref "IC3") (pin "8") (pinfunction "OUT_8") (pintype "output"))
      (node (ref "R28") (pin "2") (pinfunction "2_2") (pintype "passive"))
      (node (ref "R35") (pin "1") (pinfunction "1_1") (pintype "passive"))
    )
    (net (code "35") (name "Net-(IC3D-+IN)") (class "Default")
      (node (ref "IC3") (pin "12") (pinfunction "+IN_12") (pintype "input"))
      (node (ref "R13") (pin "2") (pinfunction "2_2") (pintype "passive"))
    )
    (net (code "36") (name "Net-(IC3D--IN)") (class "Default")
      (node (ref "IC3") (pin "13") (pinfunction "-IN_13") (pintype "input"))
      (node (ref "IC3") (pin "14") (pinfunction "OUT_14") (pintype "output"))
      (node (ref "R25") (pin "1") (pinfunction "1_1") (pintype "passive"))
    )
    (net (code "37") (name "Net-(IC4A-+IN)") (class "Default")
      (node (ref "IC4") (pin "3") (pinfunction "+IN_3") (pintype "input"))
      (node (ref "IC4") (pin "6") (pinfunction "-IN_6") (pintype "input"))
      (node (ref "R115") (pin "2") (pinfunction "2_2") (pintype "passive"))
      (node (ref "R117") (pin "2") (pinfunction "2_2") (pintype "passive"))
      (node (ref "R118") (pin "1") (pinfunction "1_1") (pintype "passive"))
    )
    (net (code "38") (name "Net-(IC4A--IN)") (class "Default")
      (node (ref "IC4") (pin "2") (pinfunction "-IN_2") (pintype "input"))
      (node (ref "R119") (pin "2") (pinfunction "2_2") (pintype "passive"))
      (node (ref "R121") (pin "1") (pinfunction "1_1") (pintype "passive"))
    )
    (net (code "39") (name "Net-(IC4A-OUT)") (class "Default")
      (node (ref "D13") (pin "A") (pinfunction "A_A") (pintype "passive"))
      (node (ref "IC4") (pin "1") (pinfunction "OUT_1") (pintype "output"))
    )
    (net (code "40") (name "Net-(IC4B-+IN)") (class "Default")
      (node (ref "IC4") (pin "5") (pinfunction "+IN_5") (pintype "input"))
      (node (ref "R119") (pin "1") (pinfunction "1_1") (pintype "passive"))
      (node (ref "R120") (pin "2") (pinfunction "2_2") (pintype "passive"))
    )
    (net (code "41") (name "Net-(IC4B-OUT)") (class "Default")
      (node (ref "D14") (pin "A") (pinfunction "A_A") (pintype "passive"))
      (node (ref "IC4") (pin "7") (pinfunction "OUT_7") (pintype "output"))
    )
    (net (code "42") (name "Net-(IC5A--IN)") (class "Default")
      (node (ref "IC5") (pin "2") (pinfunction "-IN_2") (pintype "input"))
      (node (ref "LED3") (pin "K") (pinfunction "C_K") (pintype "passive"))
      (node (ref "R10") (pin "2") (pinfunction "2_2") (pintype "passive"))
    )
    (net (code "43") (name "Net-(IC5A-OUT)") (class "Default")
      (node (ref "IC5") (pin "1") (pinfunction "OUT_1") (pintype "output"))
      (node (ref "LED3") (pin "A") (pinfunction "A_A") (pintype "passive"))
    )
    (net (code "44") (name "Net-(IC5B-+IN)") (class "Default")
      (node (ref "IC5") (pin "5") (pinfunction "+IN_5") (pintype "input"))
      (node (ref "R14") (pin "2") (pinfunction "2_2") (pintype "passive"))
    )
    (net (code "45") (name "Net-(IC5B--IN)") (class "Default")
      (node (ref "IC5") (pin "6") (pinfunction "-IN_6") (pintype "input"))
      (node (ref "IC5") (pin "7") (pinfunction "OUT_7") (pintype "output"))
      (node (ref "R12") (pin "P$2") (pinfunction "S_P$2") (pintype "passive"))
    )
    (net (code "46") (name "Net-(IC5C-+IN)") (class "Default")
      (node (ref "C21") (pin "1") (pinfunction "1_1") (pintype "passive"))
      (node (ref "IC5") (pin "10") (pinfunction "+IN_10") (pintype "input"))
      (node (ref "R12") (pin "P$3") (pinfunction "A_P$3") (pintype "passive"))
    )
    (net (code "47") (name "Net-(IC5D--IN)") (class "Default")
      (node (ref "IC5") (pin "13") (pinfunction "-IN_13") (pintype "input"))
      (node (ref "LED2") (pin "K") (pinfunction "C_K") (pintype "passive"))
      (node (ref "R9") (pin "1") (pinfunction "1_1") (pintype "passive"))
    )
    (net (code "48") (name "Net-(IC5D-OUT)") (class "Default")
      (node (ref "IC5") (pin "14") (pinfunction "OUT_14") (pintype "output"))
      (node (ref "LED2") (pin "A") (pinfunction "A_A") (pintype "passive"))
    )
    (net (code "49") (name "Net-(IC8A-+IN)") (class "Default")
      (node (ref "IC8") (pin "3") (pinfunction "+IN_3") (pintype "input"))
      (node (ref "R15") (pin "2") (pinfunction "2_2") (pintype "passive"))
    )
    (net (code "50") (name "Net-(IC8A--IN)") (class "Default")
      (node (ref "IC8") (pin "2") (pinfunction "-IN_2") (pintype "input"))
      (node (ref "R16") (pin "2") (pinfunction "2_2") (pintype "passive"))
    )
    (net (code "51") (name "Net-(IC8B-OUT)") (class "Default")
      (node (ref "D3") (pin "C") (pinfunction "C_C") (pintype "passive"))
      (node (ref "IC8") (pin "7") (pinfunction "OUT_7") (pintype "output"))
    )
    (net (code "52") (name "Net-(IC8C-OUT)") (class "Default")
      (node (ref "D9") (pin "A") (pinfunction "A_A") (pintype "passive"))
      (node (ref "IC8") (pin "8") (pinfunction "OUT_8") (pintype "output"))
    )
    (net (code "53") (name "Net-(IC8D--IN)") (class "Default")
      (node (ref "IC8") (pin "13") (pinfunction "-IN_13") (pintype "input"))
      (node (ref "LED5") (pin "K") (pinfunction "C_K") (pintype "passive"))
      (node (ref "R17") (pin "1") (pinfunction "1_1") (pintype "passive"))
    )
    (net (code "54") (name "Net-(IC8D-OUT)") (class "Default")
      (node (ref "IC8") (pin "14") (pinfunction "OUT_14") (pintype "output"))
      (node (ref "LED5") (pin "A") (pinfunction "A_A") (pintype "passive"))
    )
    (net (code "55") (name "Net-(IC9A-+IN)") (class "Default")
      (node (ref "IC9") (pin "3") (pinfunction "+IN_3") (pintype "input"))
      (node (ref "R24") (pin "P$2") (pinfunction "S_P$2") (pintype "passive"))
    )
    (net (code "56") (name "Net-(J1-3)") (class "Default")
      (node (ref "C3") (pin "1") (pinfunction "1_1") (pintype "passive"))
      (node (ref "C5") (pin "1") (pinfunction "1_1") (pintype "passive"))
      (node (ref "J1") (pin "P3") (pinfunction "3_P3") (pintype "passive"))
      (node (ref "SJ1") (pin "1") (pinfunction "1_1") (pintype "passive"))
    )
    (net (code "57") (name "Net-(J2-3)") (class "Default")
      (node (ref "J2") (pin "P3") (pinfunction "3_P3") (pintype "passive"))
      (node (ref "R1") (pin "2") (pinfunction "2_2") (pintype "passive"))
    )
    (net (code "58") (name "Net-(J3-3)") (class "Default")
      (node (ref "J3") (pin "P3") (pinfunction "3_P3") (pintype "passive"))
      (node (ref "R2") (pin "2") (pinfunction "2_2") (pintype "passive"))
    )
    (net (code "59") (name "Net-(J4-3)") (class "Default")
      (node (ref "J4") (pin "P3") (pinfunction "3_P3") (pintype "passive"))
      (node (ref "R23") (pin "2") (pinfunction "2_2") (pintype "passive"))
    )
    (net (code "60") (name "Net-(J5-3)") (class "Default")
      (node (ref "J5") (pin "P3") (pinfunction "3_P3") (pintype "passive"))
      (node (ref "R36") (pin "2") (pinfunction "2_2") (pintype "passive"))
    )
    (net (code "61") (name "Net-(J6-3)") (class "Default")
      (node (ref "J6") (pin "P3") (pinfunction "3_P3") (pintype "passive"))
      (node (ref "R22") (pin "1") (pinfunction "1_1") (pintype "passive"))
    )
    (net (code "62") (name "Net-(J7-3)") (class "Default")
      (node (ref "J7") (pin "P3") (pinfunction "3_P3") (pintype "passive"))
      (node (ref "R13") (pin "1") (pinfunction "1_1") (pintype "passive"))
    )
    (net (code "63") (name "Net-(J8-3)") (class "Default")
      (node (ref "J8") (pin "P3") (pinfunction "3_P3") (pintype "passive"))
      (node (ref "R14") (pin "1") (pinfunction "1_1") (pintype "passive"))
    )
    (net (code "64") (name "Net-(J9-3)") (class "Default")
      (node (ref "J9") (pin "P3") (pinfunction "3_P3") (pintype "passive"))
      (node (ref "R33") (pin "2") (pinfunction "2_2") (pintype "passive"))
    )
    (net (code "65") (name "Net-(J10-3)") (class "Default")
      (node (ref "J10") (pin "P3") (pinfunction "3_P3") (pintype "passive"))
      (node (ref "R16") (pin "1") (pinfunction "1_1") (pintype "passive"))
    )
    (net (code "66") (name "Net-(J11-3)") (class "Default")
      (node (ref "J11") (pin "P3") (pinfunction "3_P3") (pintype "passive"))
      (node (ref "R15") (pin "1") (pinfunction "1_1") (pintype "passive"))
    )
    (net (code "67") (name "Net-(J12-3)") (class "Default")
      (node (ref "J12") (pin "P3") (pinfunction "3_P3") (pintype "passive"))
      (node (ref "R27") (pin "2") (pinfunction "2_2") (pintype "passive"))
    )
    (net (code "68") (name "Net-(LED1-PadA)") (class "Default")
      (node (ref "LED1") (pin "A") (pinfunction "A_A") (pintype "passive"))
      (node (ref "R11") (pin "1") (pinfunction "1_1") (pintype "passive"))
    )
    (net (code "69") (name "Net-(LED4-C)") (class "Default")
      (node (ref "LED4") (pin "K") (pinfunction "C_K") (pintype "passive"))
      (node (ref "Q1") (pin "C") (pinfunction "C_C") (pintype "passive"))
    )
    (net (code "70") (name "Net-(LED4-PadA)") (class "Default")
      (node (ref "LED4") (pin "A") (pinfunction "A_A") (pintype "passive"))
      (node (ref "R112") (pin "1") (pinfunction "1_1") (pintype "passive"))
    )
    (net (code "71") (name "Net-(Q1-PadB)") (class "Default")
      (node (ref "Q1") (pin "B") (pinfunction "B_B") (pintype "passive"))
      (node (ref "R114") (pin "2") (pinfunction "2_2") (pintype "passive"))
      (node (ref "R116") (pin "2") (pinfunction "2_2") (pintype "passive"))
    )
    (net (code "72") (name "Net-(R7-E)") (class "Default")
      (node (ref "R7") (pin "P$1") (pinfunction "E_P$1") (pintype "passive"))
      (node (ref "R8") (pin "1") (pinfunction "1_1") (pintype "passive"))
    )
    (net (code "73") (name "Net-(R18-A)") (class "Default")
      (node (ref "D6") (pin "A") (pinfunction "A_A") (pintype "passive"))
      (node (ref "R18") (pin "P$3") (pinfunction "A_P$3") (pintype "passive"))
    )
    (net (code "74") (name "Net-(R19-A)") (class "Default")
      (node (ref "D5") (pin "C") (pinfunction "C_C") (pintype "passive"))
      (node (ref "R19") (pin "P$3") (pinfunction "A_P$3") (pintype "passive"))
    )
    (net (code "75") (name "SLEW") (class "Default")
      (node (ref "C10") (pin "2") (pinfunction "2_2") (pintype "passive"))
      (node (ref "C11") (pin "2") (pinfunction "2_2") (pintype "passive"))
      (node (ref "IC5") (pin "3") (pinfunction "+IN_3") (pintype "input"))
      (node (ref "J8") (pin "P2") (pinfunction "2_P2") (pintype "passive"))
      (node (ref "R2") (pin "1") (pinfunction "1_1") (pintype "passive"))
      (node (ref "R35") (pin "2") (pinfunction "2_2") (pintype "passive"))
    )
    (net (code "76") (name "THRESH") (class "Default")
      (node (ref "IC9") (pin "1") (pinfunction "OUT_1") (pintype "output"))
      (node (ref "IC9") (pin "2") (pinfunction "-IN_2") (pintype "input"))
      (node (ref "J10") (pin "P2") (pinfunction "2_P2") (pintype "passive"))
      (node (ref "R27") (pin "1") (pinfunction "1_1") (pintype "passive"))
    )
    (net (code "77") (name "VCC") (class "Default")
      (node (ref "C1") (pin "1") (pinfunction "1_1") (pintype "passive"))
      (node (ref "C13") (pin "1") (pinfunction "1_1") (pintype "passive"))
      (node (ref "C19") (pin "1") (pinfunction "1_1") (pintype "passive"))
      (node (ref "C23") (pin "1") (pinfunction "1_1") (pintype "passive"))
      (node (ref "C25") (pin "1") (pinfunction "1_1") (pintype "passive"))
      (node (ref "C56") (pin "1") (pinfunction "1_1") (pintype "passive"))
      (node (ref "C58") (pin "+") (pinfunction "+_+") (pintype "passive"))
      (node (ref "C6") (pin "1") (pinfunction "1_1") (pintype "passive"))
      (node (ref "C9") (pin "1") (pinfunction "1_1") (pintype "passive"))
      (node (ref "IC1") (pin "7") (pinfunction "V+_7") (pintype "power_in"))
      (node (ref "IC2") (pin "4") (pinfunction "V+_4") (pintype "power_in"))
      (node (ref "IC3") (pin "4") (pinfunction "V+_4") (pintype "power_in"))
      (node (ref "IC4") (pin "8") (pinfunction "V+_8") (pintype "power_in"))
      (node (ref "IC5") (pin "4") (pinfunction "V+_4") (pintype "power_in"))
      (node (ref "IC8") (pin "4") (pinfunction "V+_4") (pintype "power_in"))
      (node (ref "IC9") (pin "4") (pinfunction "V+_4") (pintype "power_in"))
      (node (ref "L1") (pin "1") (pinfunction "1_1") (pintype "passive"))
      (node (ref "R112") (pin "2") (pinfunction "2_2") (pintype "passive"))
      (node (ref "R20") (pin "1") (pinfunction "1_1") (pintype "passive"))
      (node (ref "R3") (pin "1") (pinfunction "1_1") (pintype "passive"))
    )
    (net (code "78") (name "VEE") (class "Default")
      (node (ref "C12") (pin "2") (pinfunction "2_2") (pintype "passive"))
      (node (ref "C18") (pin "2") (pinfunction "2_2") (pintype "passive"))
      (node (ref "C2") (pin "2") (pinfunction "2_2") (pintype "passive"))
      (node (ref "C20") (pin "2") (pinfunction "2_2") (pintype "passive"))
      (node (ref "C24") (pin "2") (pinfunction "2_2") (pintype "passive"))
      (node (ref "C26") (pin "2") (pinfunction "2_2") (pintype "passive"))
      (node (ref "C4") (pin "2") (pinfunction "2_2") (pintype "passive"))
      (node (ref "IC1") (pin "4") (pinfunction "V-_4") (pintype "power_in"))
      (node (ref "IC2") (pin "11") (pinfunction "V-_11") (pintype "power_in"))
      (node (ref "IC3") (pin "11") (pinfunction "V-_11") (pintype "power_in"))
      (node (ref "IC5") (pin "11") (pinfunction "V-_11") (pintype "power_in"))
      (node (ref "IC8") (pin "11") (pinfunction "V-_11") (pintype "power_in"))
      (node (ref "IC9") (pin "11") (pinfunction "V-_11") (pintype "power_in"))
      (node (ref "L2") (pin "1") (pinfunction "1_1") (pintype "passive"))
    )
    (net (code "79") (name "unconnected-(C10-Pad1)") (class "Default")
      (node (ref "C10") (pin "1") (pinfunction "1_1") (pintype "passive"))
    )
    (net (code "80") (name "unconnected-(IC9B-+IN-Pad5)") (class "Default")
      (node (ref "IC9") (pin "5") (pinfunction "+IN_5") (pintype "input"))
    )
    (net (code "81") (name "unconnected-(IC9B--IN-Pad6)") (class "Default")
      (node (ref "IC9") (pin "6") (pinfunction "-IN_6") (pintype "input"))
    )
    (net (code "82") (name "unconnected-(IC9B-OUT-Pad7)") (class "Default")
      (node (ref "IC9") (pin "7") (pinfunction "OUT_7") (pintype "output"))
    )
    (net (code "83") (name "unconnected-(IC9C-+IN-Pad10)") (class "Default")
      (node (ref "IC9") (pin "10") (pinfunction "+IN_10") (pintype "input"))
    )
    (net (code "84") (name "unconnected-(IC9C--IN-Pad9)") (class "Default")
      (node (ref "IC9") (pin "9") (pinfunction "-IN_9") (pintype "input"))
    )
    (net (code "85") (name "unconnected-(IC9C-OUT-Pad8)") (class "Default")
      (node (ref "IC9") (pin "8") (pinfunction "OUT_8") (pintype "output"))
    )
    (net (code "86") (name "unconnected-(IC9D-+IN-Pad12)") (class "Default")
      (node (ref "IC9") (pin "12") (pinfunction "+IN_12") (pintype "input"))
    )
    (net (code "87") (name "unconnected-(IC9D--IN-Pad13)") (class "Default")
      (node (ref "IC9") (pin "13") (pinfunction "-IN_13") (pintype "input"))
    )
    (net (code "88") (name "unconnected-(IC9D-OUT-Pad14)") (class "Default")
      (node (ref "IC9") (pin "14") (pinfunction "OUT_14") (pintype "output"))
    )
    (net (code "89") (name "unconnected-(J1-2-PadP2)") (class "Default")
      (node (ref "J1") (pin "P2") (pinfunction "2_P2") (pintype "passive"))
    )
    (net (code "90") (name "unconnected-(J2-2-PadP2)") (class "Default")
      (node (ref "J2") (pin "P2") (pinfunction "2_P2") (pintype "passive"))
    )
    (net (code "91") (name "unconnected-(J3-2-PadP2)") (class "Default")
      (node (ref "J3") (pin "P2") (pinfunction "2_P2") (pintype "passive"))
    )
    (net (code "92") (name "unconnected-(J4-2-PadP2)") (class "Default")
      (node (ref "J4") (pin "P2") (pinfunction "2_P2") (pintype "passive"))
    )
    (net (code "93") (name "unconnected-(J5-2-PadP2)") (class "Default")
      (node (ref "J5") (pin "P2") (pinfunction "2_P2") (pintype "passive"))
    )
    (net (code "94") (name "unconnected-(J9-2-PadP2)") (class "Default")
      (node (ref "J9") (pin "P2") (pinfunction "2_P2") (pintype "passive"))
    )
    (net (code "95") (name "unconnected-(J12-2-PadP2)") (class "Default")
      (node (ref "J12") (pin "P2") (pinfunction "2_P2") (pintype "passive"))
    )
    (net (code "96") (name "unconnected-(R12-E-PadP$1)") (class "Default")
      (node (ref "R12") (pin "P$1") (pinfunction "E_P$1") (pintype "passive"))
    )
    (net (code "97") (name "unconnected-(R18-E-PadP$1)") (class "Default")
      (node (ref "R18") (pin "P$1") (pinfunction "E_P$1") (pintype "passive"))
    )
    (net (code "98") (name "unconnected-(R19-E-PadP$1)") (class "Default")
      (node (ref "R19") (pin "P$1") (pinfunction "E_P$1") (pintype "passive"))
    )
  )
)
